# xen_teensy_motherboard_12cv_mki.net
KiCad netlist of a schematic drawn in EAGLE
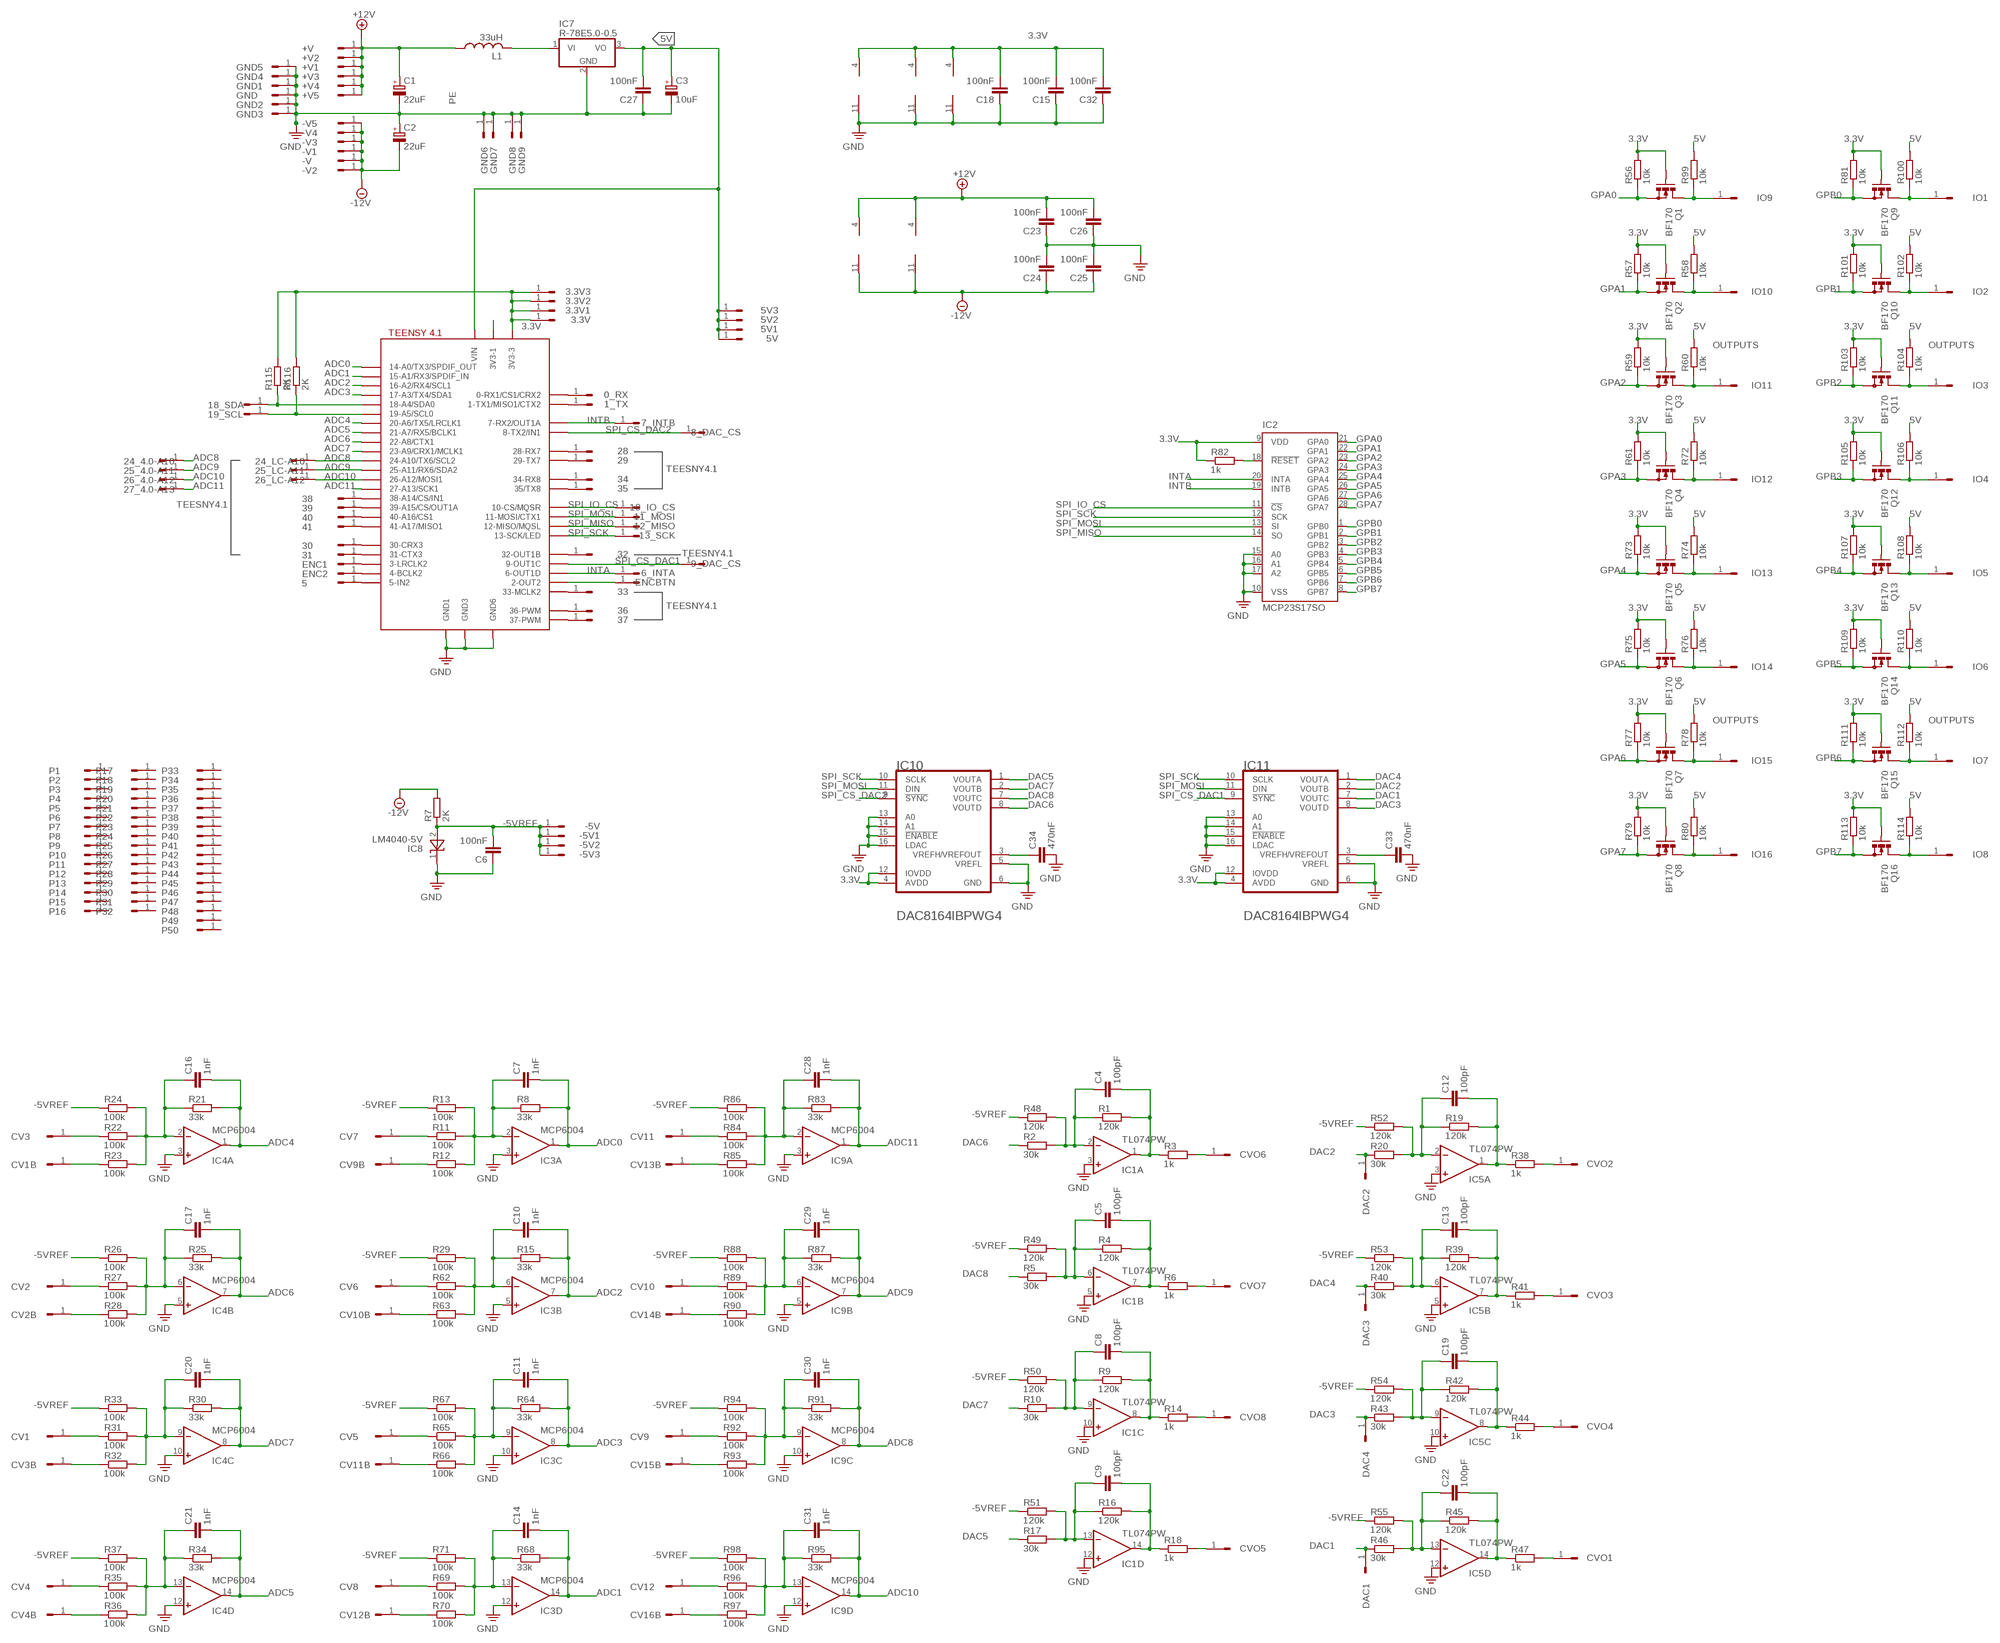
[diagram p0: schematic, sheet 1]

(export (version "E")
  (design (tool "Eeschema 10.0.6"))
  (components
    (comp (ref "+V")
      (value "HEADER/MALE/01")
      (footprint "eagle-import:HEADER_MALE_01")
      (fields (field (name "SPICEPREFIX") "X"))
      (libsource (lib "eagle-import") (part "HEADER/MALE/01"))
    )
    (comp (ref "+V1")
      (value "HEADER/MALE/01")
      (footprint "eagle-import:HEADER_MALE_01")
      (fields (field (name "SPICEPREFIX") "X"))
      (libsource (lib "eagle-import") (part "HEADER/MALE/01"))
    )
    (comp (ref "+V2")
      (value "HEADER/MALE/01")
      (footprint "eagle-import:HEADER_MALE_01")
      (fields (field (name "SPICEPREFIX") "X"))
      (libsource (lib "eagle-import") (part "HEADER/MALE/01"))
    )
    (comp (ref "+V3")
      (value "HEADER/MALE/01")
      (footprint "eagle-import:HEADER_MALE_01")
      (fields (field (name "SPICEPREFIX") "X"))
      (libsource (lib "eagle-import") (part "HEADER/MALE/01"))
    )
    (comp (ref "+V4")
      (value "HEADER/MALE/01")
      (footprint "eagle-import:HEADER_MALE_01")
      (fields (field (name "SPICEPREFIX") "X"))
      (libsource (lib "eagle-import") (part "HEADER/MALE/01"))
    )
    (comp (ref "+V5")
      (value "HEADER/MALE/01")
      (footprint "eagle-import:HEADER_MALE_01")
      (fields (field (name "SPICEPREFIX") "X"))
      (libsource (lib "eagle-import") (part "HEADER/MALE/01"))
    )
    (comp (ref "-5V")
      (value "HEADER/MALE/01")
      (footprint "eagle-import:HEADER_MALE_01")
      (fields (field (name "SPICEPREFIX") "X"))
      (libsource (lib "eagle-import") (part "HEADER/MALE/01"))
    )
    (comp (ref "-5V1")
      (value "HEADER/MALE/01")
      (footprint "eagle-import:HEADER_MALE_01")
      (fields (field (name "SPICEPREFIX") "X"))
      (libsource (lib "eagle-import") (part "HEADER/MALE/01"))
    )
    (comp (ref "-5V2")
      (value "HEADER/MALE/01")
      (footprint "eagle-import:HEADER_MALE_01")
      (fields (field (name "SPICEPREFIX") "X"))
      (libsource (lib "eagle-import") (part "HEADER/MALE/01"))
    )
    (comp (ref "-5V3")
      (value "HEADER/MALE/01")
      (footprint "eagle-import:HEADER_MALE_01")
      (fields (field (name "SPICEPREFIX") "X"))
      (libsource (lib "eagle-import") (part "HEADER/MALE/01"))
    )
    (comp (ref "-V")
      (value "HEADER/MALE/01")
      (footprint "eagle-import:HEADER_MALE_01")
      (fields (field (name "SPICEPREFIX") "X"))
      (libsource (lib "eagle-import") (part "HEADER/MALE/01"))
    )
    (comp (ref "-V1")
      (value "HEADER/MALE/01")
      (footprint "eagle-import:HEADER_MALE_01")
      (fields (field (name "SPICEPREFIX") "X"))
      (libsource (lib "eagle-import") (part "HEADER/MALE/01"))
    )
    (comp (ref "-V2")
      (value "HEADER/MALE/01")
      (footprint "eagle-import:HEADER_MALE_01")
      (fields (field (name "SPICEPREFIX") "X"))
      (libsource (lib "eagle-import") (part "HEADER/MALE/01"))
    )
    (comp (ref "-V3")
      (value "HEADER/MALE/01")
      (footprint "eagle-import:HEADER_MALE_01")
      (fields (field (name "SPICEPREFIX") "X"))
      (libsource (lib "eagle-import") (part "HEADER/MALE/01"))
    )
    (comp (ref "-V4")
      (value "HEADER/MALE/01")
      (footprint "eagle-import:HEADER_MALE_01")
      (fields (field (name "SPICEPREFIX") "X"))
      (libsource (lib "eagle-import") (part "HEADER/MALE/01"))
    )
    (comp (ref "-V5")
      (value "HEADER/MALE/01")
      (footprint "eagle-import:HEADER_MALE_01")
      (fields (field (name "SPICEPREFIX") "X"))
      (libsource (lib "eagle-import") (part "HEADER/MALE/01"))
    )
    (comp (ref "0_RX")
      (value "HEADER/MALE/01")
      (footprint "eagle-import:HEADER_MALE_01")
      (fields (field (name "SPICEPREFIX") "X"))
      (libsource (lib "eagle-import") (part "HEADER/MALE/01"))
    )
    (comp (ref "1_TX")
      (value "HEADER/MALE/01")
      (footprint "eagle-import:HEADER_MALE_01")
      (fields (field (name "SPICEPREFIX") "X"))
      (libsource (lib "eagle-import") (part "HEADER/MALE/01"))
    )
    (comp (ref "3.3V")
      (value "HEADER/MALE/01")
      (footprint "eagle-import:HEADER_MALE_01")
      (fields (field (name "SPICEPREFIX") "X"))
      (libsource (lib "eagle-import") (part "HEADER/MALE/01"))
    )
    (comp (ref "3.3V1")
      (value "HEADER/MALE/01")
      (footprint "eagle-import:HEADER_MALE_01")
      (fields (field (name "SPICEPREFIX") "X"))
      (libsource (lib "eagle-import") (part "HEADER/MALE/01"))
    )
    (comp (ref "3.3V2")
      (value "HEADER/MALE/01")
      (footprint "eagle-import:HEADER_MALE_01")
      (fields (field (name "SPICEPREFIX") "X"))
      (libsource (lib "eagle-import") (part "HEADER/MALE/01"))
    )
    (comp (ref "3.3V3")
      (value "HEADER/MALE/01")
      (footprint "eagle-import:HEADER_MALE_01")
      (fields (field (name "SPICEPREFIX") "X"))
      (libsource (lib "eagle-import") (part "HEADER/MALE/01"))
    )
    (comp (ref "5")
      (value "HEADER/MALE/01")
      (footprint "eagle-import:HEADER_MALE_01")
      (fields (field (name "SPICEPREFIX") "X"))
      (libsource (lib "eagle-import") (part "HEADER/MALE/01"))
    )
    (comp (ref "5V")
      (value "HEADER/MALE/01")
      (footprint "eagle-import:HEADER_MALE_01")
      (fields (field (name "SPICEPREFIX") "X"))
      (libsource (lib "eagle-import") (part "HEADER/MALE/01"))
    )
    (comp (ref "5V1")
      (value "HEADER/MALE/01")
      (footprint "eagle-import:HEADER_MALE_01")
      (fields (field (name "SPICEPREFIX") "X"))
      (libsource (lib "eagle-import") (part "HEADER/MALE/01"))
    )
    (comp (ref "5V2")
      (value "HEADER/MALE/01")
      (footprint "eagle-import:HEADER_MALE_01")
      (fields (field (name "SPICEPREFIX") "X"))
      (libsource (lib "eagle-import") (part "HEADER/MALE/01"))
    )
    (comp (ref "5V3")
      (value "HEADER/MALE/01")
      (footprint "eagle-import:HEADER_MALE_01")
      (fields (field (name "SPICEPREFIX") "X"))
      (libsource (lib "eagle-import") (part "HEADER/MALE/01"))
    )
    (comp (ref "6_INTA")
      (value "HEADER/MALE/01")
      (footprint "eagle-import:HEADER_MALE_01")
      (fields (field (name "SPICEPREFIX") "X"))
      (libsource (lib "eagle-import") (part "HEADER/MALE/01"))
    )
    (comp (ref "7_INTB")
      (value "HEADER/MALE/01")
      (footprint "eagle-import:HEADER_MALE_01")
      (fields (field (name "SPICEPREFIX") "X"))
      (libsource (lib "eagle-import") (part "HEADER/MALE/01"))
    )
    (comp (ref "8_DAC_CS")
      (value "HEADER/MALE/01")
      (footprint "eagle-import:HEADER_MALE_01")
      (fields (field (name "SPICEPREFIX") "X"))
      (libsource (lib "eagle-import") (part "HEADER/MALE/01"))
    )
    (comp (ref "9_DAC_CS")
      (value "HEADER/MALE/01")
      (footprint "eagle-import:HEADER_MALE_01")
      (fields (field (name "SPICEPREFIX") "X"))
      (libsource (lib "eagle-import") (part "HEADER/MALE/01"))
    )
    (comp (ref "10_IO_CS")
      (value "HEADER/MALE/01")
      (footprint "eagle-import:HEADER_MALE_01")
      (fields (field (name "SPICEPREFIX") "X"))
      (libsource (lib "eagle-import") (part "HEADER/MALE/01"))
    )
    (comp (ref "11_MOSI")
      (value "HEADER/MALE/01")
      (footprint "eagle-import:HEADER_MALE_01")
      (fields (field (name "SPICEPREFIX") "X"))
      (libsource (lib "eagle-import") (part "HEADER/MALE/01"))
    )
    (comp (ref "12_MISO")
      (value "HEADER/MALE/01")
      (footprint "eagle-import:HEADER_MALE_01")
      (fields (field (name "SPICEPREFIX") "X"))
      (libsource (lib "eagle-import") (part "HEADER/MALE/01"))
    )
    (comp (ref "13_SCK")
      (value "HEADER/MALE/01")
      (footprint "eagle-import:HEADER_MALE_01")
      (fields (field (name "SPICEPREFIX") "X"))
      (libsource (lib "eagle-import") (part "HEADER/MALE/01"))
    )
    (comp (ref "18_SDA")
      (value "HEADER/MALE/01")
      (footprint "eagle-import:HEADER_MALE_01")
      (fields (field (name "SPICEPREFIX") "X"))
      (libsource (lib "eagle-import") (part "HEADER/MALE/01"))
    )
    (comp (ref "19_SCL")
      (value "HEADER/MALE/01")
      (footprint "eagle-import:HEADER_MALE_01")
      (fields (field (name "SPICEPREFIX") "X"))
      (libsource (lib "eagle-import") (part "HEADER/MALE/01"))
    )
    (comp (ref "24_4.0-A10")
      (value "HEADER/MALE/01")
      (footprint "eagle-import:HEADER_MALE_01")
      (fields (field (name "SPICEPREFIX") "X"))
      (libsource (lib "eagle-import") (part "HEADER/MALE/01"))
    )
    (comp (ref "24_LC-A10")
      (value "HEADER/MALE/01")
      (footprint "eagle-import:HEADER_MALE_01")
      (fields (field (name "SPICEPREFIX") "X"))
      (libsource (lib "eagle-import") (part "HEADER/MALE/01"))
    )
    (comp (ref "25_4.0-A11")
      (value "HEADER/MALE/01")
      (footprint "eagle-import:HEADER_MALE_01")
      (fields (field (name "SPICEPREFIX") "X"))
      (libsource (lib "eagle-import") (part "HEADER/MALE/01"))
    )
    (comp (ref "25_LC-A11")
      (value "HEADER/MALE/01")
      (footprint "eagle-import:HEADER_MALE_01")
      (fields (field (name "SPICEPREFIX") "X"))
      (libsource (lib "eagle-import") (part "HEADER/MALE/01"))
    )
    (comp (ref "26_4.0-A12")
      (value "HEADER/MALE/01")
      (footprint "eagle-import:HEADER_MALE_01")
      (fields (field (name "SPICEPREFIX") "X"))
      (libsource (lib "eagle-import") (part "HEADER/MALE/01"))
    )
    (comp (ref "26_LC-A12")
      (value "HEADER/MALE/01")
      (footprint "eagle-import:HEADER_MALE_01")
      (fields (field (name "SPICEPREFIX") "X"))
      (libsource (lib "eagle-import") (part "HEADER/MALE/01"))
    )
    (comp (ref "27_4.0-A13")
      (value "HEADER/MALE/01")
      (footprint "eagle-import:HEADER_MALE_01")
      (fields (field (name "SPICEPREFIX") "X"))
      (libsource (lib "eagle-import") (part "HEADER/MALE/01"))
    )
    (comp (ref "28")
      (value "HEADER/MALE/01")
      (footprint "eagle-import:HEADER_MALE_01")
      (fields (field (name "SPICEPREFIX") "X"))
      (libsource (lib "eagle-import") (part "HEADER/MALE/01"))
    )
    (comp (ref "29")
      (value "HEADER/MALE/01")
      (footprint "eagle-import:HEADER_MALE_01")
      (fields (field (name "SPICEPREFIX") "X"))
      (libsource (lib "eagle-import") (part "HEADER/MALE/01"))
    )
    (comp (ref "30")
      (value "HEADER/MALE/01")
      (footprint "eagle-import:HEADER_MALE_01")
      (fields (field (name "SPICEPREFIX") "X"))
      (libsource (lib "eagle-import") (part "HEADER/MALE/01"))
    )
    (comp (ref "31")
      (value "HEADER/MALE/01")
      (footprint "eagle-import:HEADER_MALE_01")
      (fields (field (name "SPICEPREFIX") "X"))
      (libsource (lib "eagle-import") (part "HEADER/MALE/01"))
    )
    (comp (ref "32")
      (value "HEADER/MALE/01")
      (footprint "eagle-import:HEADER_MALE_01")
      (fields (field (name "SPICEPREFIX") "X"))
      (libsource (lib "eagle-import") (part "HEADER/MALE/01"))
    )
    (comp (ref "33")
      (value "HEADER/MALE/01")
      (footprint "eagle-import:HEADER_MALE_01")
      (fields (field (name "SPICEPREFIX") "X"))
      (libsource (lib "eagle-import") (part "HEADER/MALE/01"))
    )
    (comp (ref "34")
      (value "HEADER/MALE/01")
      (footprint "eagle-import:HEADER_MALE_01")
      (fields (field (name "SPICEPREFIX") "X"))
      (libsource (lib "eagle-import") (part "HEADER/MALE/01"))
    )
    (comp (ref "35")
      (value "HEADER/MALE/01")
      (footprint "eagle-import:HEADER_MALE_01")
      (fields (field (name "SPICEPREFIX") "X"))
      (libsource (lib "eagle-import") (part "HEADER/MALE/01"))
    )
    (comp (ref "36")
      (value "HEADER/MALE/01")
      (footprint "eagle-import:HEADER_MALE_01")
      (fields (field (name "SPICEPREFIX") "X"))
      (libsource (lib "eagle-import") (part "HEADER/MALE/01"))
    )
    (comp (ref "37")
      (value "HEADER/MALE/01")
      (footprint "eagle-import:HEADER_MALE_01")
      (fields (field (name "SPICEPREFIX") "X"))
      (libsource (lib "eagle-import") (part "HEADER/MALE/01"))
    )
    (comp (ref "38")
      (value "HEADER/MALE/01")
      (footprint "eagle-import:HEADER_MALE_01")
      (fields (field (name "SPICEPREFIX") "X"))
      (libsource (lib "eagle-import") (part "HEADER/MALE/01"))
    )
    (comp (ref "39")
      (value "HEADER/MALE/01")
      (footprint "eagle-import:HEADER_MALE_01")
      (fields (field (name "SPICEPREFIX") "X"))
      (libsource (lib "eagle-import") (part "HEADER/MALE/01"))
    )
    (comp (ref "40")
      (value "HEADER/MALE/01")
      (footprint "eagle-import:HEADER_MALE_01")
      (fields (field (name "SPICEPREFIX") "X"))
      (libsource (lib "eagle-import") (part "HEADER/MALE/01"))
    )
    (comp (ref "41")
      (value "HEADER/MALE/01")
      (footprint "eagle-import:HEADER_MALE_01")
      (fields (field (name "SPICEPREFIX") "X"))
      (libsource (lib "eagle-import") (part "HEADER/MALE/01"))
    )
    (comp (ref "C1")
      (value "22uF")
      (footprint "eagle-import:SV-C")
      (fields (field (name "SPICEPREFIX") "C"))
      (libsource (lib "eagle-import") (part "CAPACITOR/POLARIZEDSMDC"))
    )
    (comp (ref "C2")
      (value "22uF")
      (footprint "eagle-import:SV-C")
      (fields (field (name "SPICEPREFIX") "C"))
      (libsource (lib "eagle-import") (part "CAPACITOR/POLARIZEDSMDC"))
    )
    (comp (ref "C3")
      (value "10uF")
      (footprint "eagle-import:SV-B")
      (fields (field (name "SPICEPREFIX") "C"))
      (libsource (lib "eagle-import") (part "CAPACITOR/POLARIZEDSMDB"))
    )
    (comp (ref "C4")
      (value "100pF")
      (footprint "eagle-import:C0603")
      (libsource (lib "eagle-import") (part "CAPACITORC0603"))
    )
    (comp (ref "C5")
      (value "100pF")
      (footprint "eagle-import:C0603")
      (libsource (lib "eagle-import") (part "CAPACITORC0603"))
    )
    (comp (ref "C6")
      (value "100nF")
      (footprint "eagle-import:C0603")
      (libsource (lib "eagle-import") (part "CAPACITORC0603"))
    )
    (comp (ref "C7")
      (value "1nF")
      (footprint "eagle-import:C0603")
      (libsource (lib "eagle-import") (part "CAPACITORC0603"))
    )
    (comp (ref "C8")
      (value "100pF")
      (footprint "eagle-import:C0603")
      (libsource (lib "eagle-import") (part "CAPACITORC0603"))
    )
    (comp (ref "C9")
      (value "100pF")
      (footprint "eagle-import:C0603")
      (libsource (lib "eagle-import") (part "CAPACITORC0603"))
    )
    (comp (ref "C10")
      (value "1nF")
      (footprint "eagle-import:C0603")
      (libsource (lib "eagle-import") (part "CAPACITORC0603"))
    )
    (comp (ref "C11")
      (value "1nF")
      (footprint "eagle-import:C0603")
      (libsource (lib "eagle-import") (part "CAPACITORC0603"))
    )
    (comp (ref "C12")
      (value "100pF")
      (footprint "eagle-import:C0603")
      (libsource (lib "eagle-import") (part "CAPACITORC0603"))
    )
    (comp (ref "C13")
      (value "100pF")
      (footprint "eagle-import:C0603")
      (libsource (lib "eagle-import") (part "CAPACITORC0603"))
    )
    (comp (ref "C14")
      (value "1nF")
      (footprint "eagle-import:C0603")
      (libsource (lib "eagle-import") (part "CAPACITORC0603"))
    )
    (comp (ref "C15")
      (value "100nF")
      (footprint "eagle-import:C0603")
      (libsource (lib "eagle-import") (part "CAPACITORC0603"))
    )
    (comp (ref "C16")
      (value "1nF")
      (footprint "eagle-import:C0603")
      (libsource (lib "eagle-import") (part "CAPACITORC0603"))
    )
    (comp (ref "C17")
      (value "1nF")
      (footprint "eagle-import:C0603")
      (libsource (lib "eagle-import") (part "CAPACITORC0603"))
    )
    (comp (ref "C18")
      (value "100nF")
      (footprint "eagle-import:C0603")
      (libsource (lib "eagle-import") (part "CAPACITORC0603"))
    )
    (comp (ref "C19")
      (value "100pF")
      (footprint "eagle-import:C0603")
      (libsource (lib "eagle-import") (part "CAPACITORC0603"))
    )
    (comp (ref "C20")
      (value "1nF")
      (footprint "eagle-import:C0603")
      (libsource (lib "eagle-import") (part "CAPACITORC0603"))
    )
    (comp (ref "C21")
      (value "1nF")
      (footprint "eagle-import:C0603")
      (libsource (lib "eagle-import") (part "CAPACITORC0603"))
    )
    (comp (ref "C22")
      (value "100pF")
      (footprint "eagle-import:C0603")
      (libsource (lib "eagle-import") (part "CAPACITORC0603"))
    )
    (comp (ref "C23")
      (value "100nF")
      (footprint "eagle-import:C0603")
      (libsource (lib "eagle-import") (part "CAPACITORC0603"))
    )
    (comp (ref "C24")
      (value "100nF")
      (footprint "eagle-import:C0603")
      (libsource (lib "eagle-import") (part "CAPACITORC0603"))
    )
    (comp (ref "C25")
      (value "100nF")
      (footprint "eagle-import:C0603")
      (libsource (lib "eagle-import") (part "CAPACITORC0603"))
    )
    (comp (ref "C26")
      (value "100nF")
      (footprint "eagle-import:C0603")
      (libsource (lib "eagle-import") (part "CAPACITORC0603"))
    )
    (comp (ref "C27")
      (value "100nF")
      (footprint "eagle-import:C0603")
      (libsource (lib "eagle-import") (part "CAPACITORC0603"))
    )
    (comp (ref "C28")
      (value "1nF")
      (footprint "eagle-import:C0603")
      (libsource (lib "eagle-import") (part "CAPACITORC0603"))
    )
    (comp (ref "C29")
      (value "1nF")
      (footprint "eagle-import:C0603")
      (libsource (lib "eagle-import") (part "CAPACITORC0603"))
    )
    (comp (ref "C30")
      (value "1nF")
      (footprint "eagle-import:C0603")
      (libsource (lib "eagle-import") (part "CAPACITORC0603"))
    )
    (comp (ref "C31")
      (value "1nF")
      (footprint "eagle-import:C0603")
      (libsource (lib "eagle-import") (part "CAPACITORC0603"))
    )
    (comp (ref "C32")
      (value "100nF")
      (footprint "eagle-import:C0603")
      (libsource (lib "eagle-import") (part "CAPACITORC0603"))
    )
    (comp (ref "C33")
      (value "470nF")
      (footprint "eagle-import:C0603")
      (libsource (lib "eagle-import") (part "CAPACITORC0603"))
    )
    (comp (ref "C34")
      (value "470nF")
      (footprint "eagle-import:C0603")
      (libsource (lib "eagle-import") (part "CAPACITORC0603"))
    )
    (comp (ref "CV1")
      (value "HEADER/MALE/01")
      (footprint "eagle-import:HEADER_MALE_01")
      (fields (field (name "SPICEPREFIX") "X"))
      (libsource (lib "eagle-import") (part "HEADER/MALE/01"))
    )
    (comp (ref "CV1B")
      (value "HEADER/MALE/01")
      (footprint "eagle-import:HEADER_MALE_01")
      (fields (field (name "SPICEPREFIX") "X"))
      (libsource (lib "eagle-import") (part "HEADER/MALE/01"))
    )
    (comp (ref "CV2")
      (value "HEADER/MALE/01")
      (footprint "eagle-import:HEADER_MALE_01")
      (fields (field (name "SPICEPREFIX") "X"))
      (libsource (lib "eagle-import") (part "HEADER/MALE/01"))
    )
    (comp (ref "CV2B")
      (value "HEADER/MALE/01")
      (footprint "eagle-import:HEADER_MALE_01")
      (fields (field (name "SPICEPREFIX") "X"))
      (libsource (lib "eagle-import") (part "HEADER/MALE/01"))
    )
    (comp (ref "CV3")
      (value "HEADER/MALE/01")
      (footprint "eagle-import:HEADER_MALE_01")
      (fields (field (name "SPICEPREFIX") "X"))
      (libsource (lib "eagle-import") (part "HEADER/MALE/01"))
    )
    (comp (ref "CV3B")
      (value "HEADER/MALE/01")
      (footprint "eagle-import:HEADER_MALE_01")
      (fields (field (name "SPICEPREFIX") "X"))
      (libsource (lib "eagle-import") (part "HEADER/MALE/01"))
    )
    (comp (ref "CV4")
      (value "HEADER/MALE/01")
      (footprint "eagle-import:HEADER_MALE_01")
      (fields (field (name "SPICEPREFIX") "X"))
      (libsource (lib "eagle-import") (part "HEADER/MALE/01"))
    )
    (comp (ref "CV4B")
      (value "HEADER/MALE/01")
      (footprint "eagle-import:HEADER_MALE_01")
      (fields (field (name "SPICEPREFIX") "X"))
      (libsource (lib "eagle-import") (part "HEADER/MALE/01"))
    )
    (comp (ref "CV5")
      (value "HEADER/MALE/01")
      (footprint "eagle-import:HEADER_MALE_01")
      (fields (field (name "SPICEPREFIX") "X"))
      (libsource (lib "eagle-import") (part "HEADER/MALE/01"))
    )
    (comp (ref "CV6")
      (value "HEADER/MALE/01")
      (footprint "eagle-import:HEADER_MALE_01")
      (fields (field (name "SPICEPREFIX") "X"))
      (libsource (lib "eagle-import") (part "HEADER/MALE/01"))
    )
    (comp (ref "CV7")
      (value "HEADER/MALE/01")
      (footprint "eagle-import:HEADER_MALE_01")
      (fields (field (name "SPICEPREFIX") "X"))
      (libsource (lib "eagle-import") (part "HEADER/MALE/01"))
    )
    (comp (ref "CV8")
      (value "HEADER/MALE/01")
      (footprint "eagle-import:HEADER_MALE_01")
      (fields (field (name "SPICEPREFIX") "X"))
      (libsource (lib "eagle-import") (part "HEADER/MALE/01"))
    )
    (comp (ref "CV9")
      (value "HEADER/MALE/01")
      (footprint "eagle-import:HEADER_MALE_01")
      (fields (field (name "SPICEPREFIX") "X"))
      (libsource (lib "eagle-import") (part "HEADER/MALE/01"))
    )
    (comp (ref "CV9B")
      (value "HEADER/MALE/01")
      (footprint "eagle-import:HEADER_MALE_01")
      (fields (field (name "SPICEPREFIX") "X"))
      (libsource (lib "eagle-import") (part "HEADER/MALE/01"))
    )
    (comp (ref "CV10")
      (value "HEADER/MALE/01")
      (footprint "eagle-import:HEADER_MALE_01")
      (fields (field (name "SPICEPREFIX") "X"))
      (libsource (lib "eagle-import") (part "HEADER/MALE/01"))
    )
    (comp (ref "CV10B")
      (value "HEADER/MALE/01")
      (footprint "eagle-import:HEADER_MALE_01")
      (fields (field (name "SPICEPREFIX") "X"))
      (libsource (lib "eagle-import") (part "HEADER/MALE/01"))
    )
    (comp (ref "CV11")
      (value "HEADER/MALE/01")
      (footprint "eagle-import:HEADER_MALE_01")
      (fields (field (name "SPICEPREFIX") "X"))
      (libsource (lib "eagle-import") (part "HEADER/MALE/01"))
    )
    (comp (ref "CV11B")
      (value "HEADER/MALE/01")
      (footprint "eagle-import:HEADER_MALE_01")
      (fields (field (name "SPICEPREFIX") "X"))
      (libsource (lib "eagle-import") (part "HEADER/MALE/01"))
    )
    (comp (ref "CV12")
      (value "HEADER/MALE/01")
      (footprint "eagle-import:HEADER_MALE_01")
      (fields (field (name "SPICEPREFIX") "X"))
      (libsource (lib "eagle-import") (part "HEADER/MALE/01"))
    )
    (comp (ref "CV12B")
      (value "HEADER/MALE/01")
      (footprint "eagle-import:HEADER_MALE_01")
      (fields (field (name "SPICEPREFIX") "X"))
      (libsource (lib "eagle-import") (part "HEADER/MALE/01"))
    )
    (comp (ref "CV13B")
      (value "HEADER/MALE/01")
      (footprint "eagle-import:HEADER_MALE_01")
      (fields (field (name "SPICEPREFIX") "X"))
      (libsource (lib "eagle-import") (part "HEADER/MALE/01"))
    )
    (comp (ref "CV14B")
      (value "HEADER/MALE/01")
      (footprint "eagle-import:HEADER_MALE_01")
      (fields (field (name "SPICEPREFIX") "X"))
      (libsource (lib "eagle-import") (part "HEADER/MALE/01"))
    )
    (comp (ref "CV15B")
      (value "HEADER/MALE/01")
      (footprint "eagle-import:HEADER_MALE_01")
      (fields (field (name "SPICEPREFIX") "X"))
      (libsource (lib "eagle-import") (part "HEADER/MALE/01"))
    )
    (comp (ref "CV16B")
      (value "HEADER/MALE/01")
      (footprint "eagle-import:HEADER_MALE_01")
      (fields (field (name "SPICEPREFIX") "X"))
      (libsource (lib "eagle-import") (part "HEADER/MALE/01"))
    )
    (comp (ref "CVO1")
      (value "HEADER/MALE/01")
      (footprint "eagle-import:HEADER_MALE_01")
      (fields (field (name "SPICEPREFIX") "X"))
      (libsource (lib "eagle-import") (part "HEADER/MALE/01"))
    )
    (comp (ref "CVO2")
      (value "HEADER/MALE/01")
      (footprint "eagle-import:HEADER_MALE_01")
      (fields (field (name "SPICEPREFIX") "X"))
      (libsource (lib "eagle-import") (part "HEADER/MALE/01"))
    )
    (comp (ref "CVO3")
      (value "HEADER/MALE/01")
      (footprint "eagle-import:HEADER_MALE_01")
      (fields (field (name "SPICEPREFIX") "X"))
      (libsource (lib "eagle-import") (part "HEADER/MALE/01"))
    )
    (comp (ref "CVO4")
      (value "HEADER/MALE/01")
      (footprint "eagle-import:HEADER_MALE_01")
      (fields (field (name "SPICEPREFIX") "X"))
      (libsource (lib "eagle-import") (part "HEADER/MALE/01"))
    )
    (comp (ref "CVO5")
      (value "HEADER/MALE/01")
      (footprint "eagle-import:HEADER_MALE_01")
      (fields (field (name "SPICEPREFIX") "X"))
      (libsource (lib "eagle-import") (part "HEADER/MALE/01"))
    )
    (comp (ref "CVO6")
      (value "HEADER/MALE/01")
      (footprint "eagle-import:HEADER_MALE_01")
      (fields (field (name "SPICEPREFIX") "X"))
      (libsource (lib "eagle-import") (part "HEADER/MALE/01"))
    )
    (comp (ref "CVO7")
      (value "HEADER/MALE/01")
      (footprint "eagle-import:HEADER_MALE_01")
      (fields (field (name "SPICEPREFIX") "X"))
      (libsource (lib "eagle-import") (part "HEADER/MALE/01"))
    )
    (comp (ref "CVO8")
      (value "HEADER/MALE/01")
      (footprint "eagle-import:HEADER_MALE_01")
      (fields (field (name "SPICEPREFIX") "X"))
      (libsource (lib "eagle-import") (part "HEADER/MALE/01"))
    )
    (comp (ref "DAC1")
      (value "HEADER/MALE/01")
      (footprint "eagle-import:HEADER_MALE_01")
      (fields (field (name "SPICEPREFIX") "X"))
      (libsource (lib "eagle-import") (part "HEADER/MALE/01"))
    )
    (comp (ref "DAC2")
      (value "HEADER/MALE/01")
      (footprint "eagle-import:HEADER_MALE_01")
      (fields (field (name "SPICEPREFIX") "X"))
      (libsource (lib "eagle-import") (part "HEADER/MALE/01"))
    )
    (comp (ref "DAC3")
      (value "HEADER/MALE/01")
      (footprint "eagle-import:HEADER_MALE_01")
      (fields (field (name "SPICEPREFIX") "X"))
      (libsource (lib "eagle-import") (part "HEADER/MALE/01"))
    )
    (comp (ref "DAC4")
      (value "HEADER/MALE/01")
      (footprint "eagle-import:HEADER_MALE_01")
      (fields (field (name "SPICEPREFIX") "X"))
      (libsource (lib "eagle-import") (part "HEADER/MALE/01"))
    )
    (comp (ref "ENC1")
      (value "HEADER/MALE/01")
      (footprint "eagle-import:HEADER_MALE_01")
      (fields (field (name "SPICEPREFIX") "X"))
      (libsource (lib "eagle-import") (part "HEADER/MALE/01"))
    )
    (comp (ref "ENC2")
      (value "HEADER/MALE/01")
      (footprint "eagle-import:HEADER_MALE_01")
      (fields (field (name "SPICEPREFIX") "X"))
      (libsource (lib "eagle-import") (part "HEADER/MALE/01"))
    )
    (comp (ref "ENCBTN")
      (value "HEADER/MALE/01")
      (footprint "eagle-import:HEADER_MALE_01")
      (fields (field (name "SPICEPREFIX") "X"))
      (libsource (lib "eagle-import") (part "HEADER/MALE/01"))
    )
    (comp (ref "GND")
      (value "HEADER/MALE/01")
      (footprint "eagle-import:HEADER_MALE_01")
      (fields (field (name "SPICEPREFIX") "X"))
      (libsource (lib "eagle-import") (part "HEADER/MALE/01"))
    )
    (comp (ref "GND1")
      (value "HEADER/MALE/01")
      (footprint "eagle-import:HEADER_MALE_01")
      (fields (field (name "SPICEPREFIX") "X"))
      (libsource (lib "eagle-import") (part "HEADER/MALE/01"))
    )
    (comp (ref "GND2")
      (value "HEADER/MALE/01")
      (footprint "eagle-import:HEADER_MALE_01")
      (fields (field (name "SPICEPREFIX") "X"))
      (libsource (lib "eagle-import") (part "HEADER/MALE/01"))
    )
    (comp (ref "GND3")
      (value "HEADER/MALE/01")
      (footprint "eagle-import:HEADER_MALE_01")
      (fields (field (name "SPICEPREFIX") "X"))
      (libsource (lib "eagle-import") (part "HEADER/MALE/01"))
    )
    (comp (ref "GND4")
      (value "HEADER/MALE/01")
      (footprint "eagle-import:HEADER_MALE_01")
      (fields (field (name "SPICEPREFIX") "X"))
      (libsource (lib "eagle-import") (part "HEADER/MALE/01"))
    )
    (comp (ref "GND5")
      (value "HEADER/MALE/01")
      (footprint "eagle-import:HEADER_MALE_01")
      (fields (field (name "SPICEPREFIX") "X"))
      (libsource (lib "eagle-import") (part "HEADER/MALE/01"))
    )
    (comp (ref "GND6")
      (value "HEADER/MALE/01")
      (footprint "eagle-import:HEADER_MALE_01")
      (fields (field (name "SPICEPREFIX") "X"))
      (libsource (lib "eagle-import") (part "HEADER/MALE/01"))
    )
    (comp (ref "GND7")
      (value "HEADER/MALE/01")
      (footprint "eagle-import:HEADER_MALE_01")
      (fields (field (name "SPICEPREFIX") "X"))
      (libsource (lib "eagle-import") (part "HEADER/MALE/01"))
    )
    (comp (ref "GND8")
      (value "HEADER/MALE/01")
      (footprint "eagle-import:HEADER_MALE_01")
      (fields (field (name "SPICEPREFIX") "X"))
      (libsource (lib "eagle-import") (part "HEADER/MALE/01"))
    )
    (comp (ref "GND9")
      (value "HEADER/MALE/01")
      (footprint "eagle-import:HEADER_MALE_01")
      (fields (field (name "SPICEPREFIX") "X"))
      (libsource (lib "eagle-import") (part "HEADER/MALE/01"))
    )
    (comp (ref "IC1")
      (value "TL074PW")
      (footprint "eagle-import:TSSOP14")
      (libsource (lib "eagle-import") (part "TL074PW"))
    )
    (comp (ref "IC2")
      (value "MCP23S17SO")
      (footprint "eagle-import:SO28W")
      (fields (field (name "MF") "MICROCHIP") (field (name "MPN") "MCP23S17-E/SO"))
      (libsource (lib "eagle-import") (part "MCP23S17SO"))
    )
    (comp (ref "IC3")
      (value "MCP6004")
      (footprint "eagle-import:TSSOP14")
      (libsource (lib "eagle-import") (part "TL074PW"))
    )
    (comp (ref "IC4")
      (value "MCP6004")
      (footprint "eagle-import:TSSOP14")
      (libsource (lib "eagle-import") (part "TL074PW"))
    )
    (comp (ref "IC5")
      (value "TL074PW")
      (footprint "eagle-import:TSSOP14")
      (libsource (lib "eagle-import") (part "TL074PW"))
    )
    (comp (ref "IC6")
      (value "TEENSY41-OUTER")
      (footprint "eagle-import:TENNSY41-OUTER")
      (libsource (lib "eagle-import") (part "TEENSY41-OUTER"))
    )
    (comp (ref "IC7")
      (value "R-78E5.0-0.5")
      (footprint "eagle-import:WE78")
      (libsource (lib "eagle-import") (part "WE173950378"))
    )
    (comp (ref "IC8")
      (value "LM4040-5V")
      (footprint "eagle-import:SOT-23")
      (libsource (lib "eagle-import") (part "LM4040CYM3-2.5"))
    )
    (comp (ref "IC9")
      (value "MCP6004")
      (footprint "eagle-import:TSSOP14")
      (libsource (lib "eagle-import") (part "TL074PW"))
    )
    (comp (ref "IC10")
      (value "TEXAS_INSTRUMENTS_DAC8164IBPWG4TEXAS_INSTRUMENTS_DAC8164IBPWG4_0_1")
      (footprint "eagle-import:TEXAS_INSTRUMENTS_DAC8164IBPWG4_1")
      (fields (field (name "MF") "Texas Instruments") (field (name "MPN") "DAC8164IBPWG4"))
      (libsource (lib "eagle-import") (part "TEXAS_INSTRUMENTS_DAC8164IBPWG4TEXAS_INSTRUMENTS_DAC8164IBPWG4_0_1"))
    )
    (comp (ref "IC11")
      (value "TEXAS_INSTRUMENTS_DAC8164IBPWG4TEXAS_INSTRUMENTS_DAC8164IBPWG4_0_1")
      (footprint "eagle-import:TEXAS_INSTRUMENTS_DAC8164IBPWG4_1")
      (fields (field (name "MF") "Texas Instruments") (field (name "MPN") "DAC8164IBPWG4"))
      (libsource (lib "eagle-import") (part "TEXAS_INSTRUMENTS_DAC8164IBPWG4TEXAS_INSTRUMENTS_DAC8164IBPWG4_0_1"))
    )
    (comp (ref "IO1")
      (value "HEADER/MALE/01")
      (footprint "eagle-import:HEADER_MALE_01")
      (fields (field (name "SPICEPREFIX") "X"))
      (libsource (lib "eagle-import") (part "HEADER/MALE/01"))
    )
    (comp (ref "IO2")
      (value "HEADER/MALE/01")
      (footprint "eagle-import:HEADER_MALE_01")
      (fields (field (name "SPICEPREFIX") "X"))
      (libsource (lib "eagle-import") (part "HEADER/MALE/01"))
    )
    (comp (ref "IO3")
      (value "HEADER/MALE/01")
      (footprint "eagle-import:HEADER_MALE_01")
      (fields (field (name "SPICEPREFIX") "X"))
      (libsource (lib "eagle-import") (part "HEADER/MALE/01"))
    )
    (comp (ref "IO4")
      (value "HEADER/MALE/01")
      (footprint "eagle-import:HEADER_MALE_01")
      (fields (field (name "SPICEPREFIX") "X"))
      (libsource (lib "eagle-import") (part "HEADER/MALE/01"))
    )
    (comp (ref "IO5")
      (value "HEADER/MALE/01")
      (footprint "eagle-import:HEADER_MALE_01")
      (fields (field (name "SPICEPREFIX") "X"))
      (libsource (lib "eagle-import") (part "HEADER/MALE/01"))
    )
    (comp (ref "IO6")
      (value "HEADER/MALE/01")
      (footprint "eagle-import:HEADER_MALE_01")
      (fields (field (name "SPICEPREFIX") "X"))
      (libsource (lib "eagle-import") (part "HEADER/MALE/01"))
    )
    (comp (ref "IO7")
      (value "HEADER/MALE/01")
      (footprint "eagle-import:HEADER_MALE_01")
      (fields (field (name "SPICEPREFIX") "X"))
      (libsource (lib "eagle-import") (part "HEADER/MALE/01"))
    )
    (comp (ref "IO8")
      (value "HEADER/MALE/01")
      (footprint "eagle-import:HEADER_MALE_01")
      (fields (field (name "SPICEPREFIX") "X"))
      (libsource (lib "eagle-import") (part "HEADER/MALE/01"))
    )
    (comp (ref "IO9")
      (value "HEADER/MALE/01")
      (footprint "eagle-import:HEADER_MALE_01")
      (fields (field (name "SPICEPREFIX") "X"))
      (libsource (lib "eagle-import") (part "HEADER/MALE/01"))
    )
    (comp (ref "IO10")
      (value "HEADER/MALE/01")
      (footprint "eagle-import:HEADER_MALE_01")
      (fields (field (name "SPICEPREFIX") "X"))
      (libsource (lib "eagle-import") (part "HEADER/MALE/01"))
    )
    (comp (ref "IO11")
      (value "HEADER/MALE/01")
      (footprint "eagle-import:HEADER_MALE_01")
      (fields (field (name "SPICEPREFIX") "X"))
      (libsource (lib "eagle-import") (part "HEADER/MALE/01"))
    )
    (comp (ref "IO12")
      (value "HEADER/MALE/01")
      (footprint "eagle-import:HEADER_MALE_01")
      (fields (field (name "SPICEPREFIX") "X"))
      (libsource (lib "eagle-import") (part "HEADER/MALE/01"))
    )
    (comp (ref "IO13")
      (value "HEADER/MALE/01")
      (footprint "eagle-import:HEADER_MALE_01")
      (fields (field (name "SPICEPREFIX") "X"))
      (libsource (lib "eagle-import") (part "HEADER/MALE/01"))
    )
    (comp (ref "IO14")
      (value "HEADER/MALE/01")
      (footprint "eagle-import:HEADER_MALE_01")
      (fields (field (name "SPICEPREFIX") "X"))
      (libsource (lib "eagle-import") (part "HEADER/MALE/01"))
    )
    (comp (ref "IO15")
      (value "HEADER/MALE/01")
      (footprint "eagle-import:HEADER_MALE_01")
      (fields (field (name "SPICEPREFIX") "X"))
      (libsource (lib "eagle-import") (part "HEADER/MALE/01"))
    )
    (comp (ref "IO16")
      (value "HEADER/MALE/01")
      (footprint "eagle-import:HEADER_MALE_01")
      (fields (field (name "SPICEPREFIX") "X"))
      (libsource (lib "eagle-import") (part "HEADER/MALE/01"))
    )
    (comp (ref "L1")
      (value "33uH")
      (footprint "eagle-import:L2012C")
      (libsource (lib "eagle-import") (part "INDUCTORL2012C"))
    )
    (comp (ref "P1")
      (value "HEADER/MALE/01NOBORDER")
      (footprint "eagle-import:HEADER_MALE_01_NOBORDER")
      (fields (field (name "SPICEPREFIX") "X"))
      (libsource (lib "eagle-import") (part "HEADER/MALE/01NOBORDER"))
    )
    (comp (ref "P2")
      (value "HEADER/MALE/01NOBORDER")
      (footprint "eagle-import:HEADER_MALE_01_NOBORDER")
      (fields (field (name "SPICEPREFIX") "X"))
      (libsource (lib "eagle-import") (part "HEADER/MALE/01NOBORDER"))
    )
    (comp (ref "P3")
      (value "HEADER/MALE/01NOBORDER")
      (footprint "eagle-import:HEADER_MALE_01_NOBORDER")
      (fields (field (name "SPICEPREFIX") "X"))
      (libsource (lib "eagle-import") (part "HEADER/MALE/01NOBORDER"))
    )
    (comp (ref "P4")
      (value "HEADER/MALE/01NOBORDER")
      (footprint "eagle-import:HEADER_MALE_01_NOBORDER")
      (fields (field (name "SPICEPREFIX") "X"))
      (libsource (lib "eagle-import") (part "HEADER/MALE/01NOBORDER"))
    )
    (comp (ref "P5")
      (value "HEADER/MALE/01NOBORDER")
      (footprint "eagle-import:HEADER_MALE_01_NOBORDER")
      (fields (field (name "SPICEPREFIX") "X"))
      (libsource (lib "eagle-import") (part "HEADER/MALE/01NOBORDER"))
    )
    (comp (ref "P6")
      (value "HEADER/MALE/01NOBORDER")
      (footprint "eagle-import:HEADER_MALE_01_NOBORDER")
      (fields (field (name "SPICEPREFIX") "X"))
      (libsource (lib "eagle-import") (part "HEADER/MALE/01NOBORDER"))
    )
    (comp (ref "P7")
      (value "HEADER/MALE/01NOBORDER")
      (footprint "eagle-import:HEADER_MALE_01_NOBORDER")
      (fields (field (name "SPICEPREFIX") "X"))
      (libsource (lib "eagle-import") (part "HEADER/MALE/01NOBORDER"))
    )
    (comp (ref "P8")
      (value "HEADER/MALE/01NOBORDER")
      (footprint "eagle-import:HEADER_MALE_01_NOBORDER")
      (fields (field (name "SPICEPREFIX") "X"))
      (libsource (lib "eagle-import") (part "HEADER/MALE/01NOBORDER"))
    )
    (comp (ref "P9")
      (value "HEADER/MALE/01NOBORDER")
      (footprint "eagle-import:HEADER_MALE_01_NOBORDER")
      (fields (field (name "SPICEPREFIX") "X"))
      (libsource (lib "eagle-import") (part "HEADER/MALE/01NOBORDER"))
    )
    (comp (ref "P10")
      (value "HEADER/MALE/01NOBORDER")
      (footprint "eagle-import:HEADER_MALE_01_NOBORDER")
      (fields (field (name "SPICEPREFIX") "X"))
      (libsource (lib "eagle-import") (part "HEADER/MALE/01NOBORDER"))
    )
    (comp (ref "P11")
      (value "HEADER/MALE/01NOBORDER")
      (footprint "eagle-import:HEADER_MALE_01_NOBORDER")
      (fields (field (name "SPICEPREFIX") "X"))
      (libsource (lib "eagle-import") (part "HEADER/MALE/01NOBORDER"))
    )
    (comp (ref "P12")
      (value "HEADER/MALE/01NOBORDER")
      (footprint "eagle-import:HEADER_MALE_01_NOBORDER")
      (fields (field (name "SPICEPREFIX") "X"))
      (libsource (lib "eagle-import") (part "HEADER/MALE/01NOBORDER"))
    )
    (comp (ref "P13")
      (value "HEADER/MALE/01NOBORDER")
      (footprint "eagle-import:HEADER_MALE_01_NOBORDER")
      (fields (field (name "SPICEPREFIX") "X"))
      (libsource (lib "eagle-import") (part "HEADER/MALE/01NOBORDER"))
    )
    (comp (ref "P14")
      (value "HEADER/MALE/01NOBORDER")
      (footprint "eagle-import:HEADER_MALE_01_NOBORDER")
      (fields (field (name "SPICEPREFIX") "X"))
      (libsource (lib "eagle-import") (part "HEADER/MALE/01NOBORDER"))
    )
    (comp (ref "P15")
      (value "HEADER/MALE/01NOBORDER")
      (footprint "eagle-import:HEADER_MALE_01_NOBORDER")
      (fields (field (name "SPICEPREFIX") "X"))
      (libsource (lib "eagle-import") (part "HEADER/MALE/01NOBORDER"))
    )
    (comp (ref "P16")
      (value "HEADER/MALE/01NOBORDER")
      (footprint "eagle-import:HEADER_MALE_01_NOBORDER")
      (fields (field (name "SPICEPREFIX") "X"))
      (libsource (lib "eagle-import") (part "HEADER/MALE/01NOBORDER"))
    )
    (comp (ref "P17")
      (value "HEADER/MALE/01NOBORDER")
      (footprint "eagle-import:HEADER_MALE_01_NOBORDER")
      (fields (field (name "SPICEPREFIX") "X"))
      (libsource (lib "eagle-import") (part "HEADER/MALE/01NOBORDER"))
    )
    (comp (ref "P18")
      (value "HEADER/MALE/01NOBORDER")
      (footprint "eagle-import:HEADER_MALE_01_NOBORDER")
      (fields (field (name "SPICEPREFIX") "X"))
      (libsource (lib "eagle-import") (part "HEADER/MALE/01NOBORDER"))
    )
    (comp (ref "P19")
      (value "HEADER/MALE/01NOBORDER")
      (footprint "eagle-import:HEADER_MALE_01_NOBORDER")
      (fields (field (name "SPICEPREFIX") "X"))
      (libsource (lib "eagle-import") (part "HEADER/MALE/01NOBORDER"))
    )
    (comp (ref "P20")
      (value "HEADER/MALE/01NOBORDER")
      (footprint "eagle-import:HEADER_MALE_01_NOBORDER")
      (fields (field (name "SPICEPREFIX") "X"))
      (libsource (lib "eagle-import") (part "HEADER/MALE/01NOBORDER"))
    )
    (comp (ref "P21")
      (value "HEADER/MALE/01NOBORDER")
      (footprint "eagle-import:HEADER_MALE_01_NOBORDER")
      (fields (field (name "SPICEPREFIX") "X"))
      (libsource (lib "eagle-import") (part "HEADER/MALE/01NOBORDER"))
    )
    (comp (ref "P22")
      (value "HEADER/MALE/01NOBORDER")
      (footprint "eagle-import:HEADER_MALE_01_NOBORDER")
      (fields (field (name "SPICEPREFIX") "X"))
      (libsource (lib "eagle-import") (part "HEADER/MALE/01NOBORDER"))
    )
    (comp (ref "P23")
      (value "HEADER/MALE/01NOBORDER")
      (footprint "eagle-import:HEADER_MALE_01_NOBORDER")
      (fields (field (name "SPICEPREFIX") "X"))
      (libsource (lib "eagle-import") (part "HEADER/MALE/01NOBORDER"))
    )
    (comp (ref "P24")
      (value "HEADER/MALE/01NOBORDER")
      (footprint "eagle-import:HEADER_MALE_01_NOBORDER")
      (fields (field (name "SPICEPREFIX") "X"))
      (libsource (lib "eagle-import") (part "HEADER/MALE/01NOBORDER"))
    )
    (comp (ref "P25")
      (value "HEADER/MALE/01NOBORDER")
      (footprint "eagle-import:HEADER_MALE_01_NOBORDER")
      (fields (field (name "SPICEPREFIX") "X"))
      (libsource (lib "eagle-import") (part "HEADER/MALE/01NOBORDER"))
    )
    (comp (ref "P26")
      (value "HEADER/MALE/01NOBORDER")
      (footprint "eagle-import:HEADER_MALE_01_NOBORDER")
      (fields (field (name "SPICEPREFIX") "X"))
      (libsource (lib "eagle-import") (part "HEADER/MALE/01NOBORDER"))
    )
    (comp (ref "P27")
      (value "HEADER/MALE/01NOBORDER")
      (footprint "eagle-import:HEADER_MALE_01_NOBORDER")
      (fields (field (name "SPICEPREFIX") "X"))
      (libsource (lib "eagle-import") (part "HEADER/MALE/01NOBORDER"))
    )
    (comp (ref "P28")
      (value "HEADER/MALE/01NOBORDER")
      (footprint "eagle-import:HEADER_MALE_01_NOBORDER")
      (fields (field (name "SPICEPREFIX") "X"))
      (libsource (lib "eagle-import") (part "HEADER/MALE/01NOBORDER"))
    )
    (comp (ref "P29")
      (value "HEADER/MALE/01NOBORDER")
      (footprint "eagle-import:HEADER_MALE_01_NOBORDER")
      (fields (field (name "SPICEPREFIX") "X"))
      (libsource (lib "eagle-import") (part "HEADER/MALE/01NOBORDER"))
    )
    (comp (ref "P30")
      (value "HEADER/MALE/01NOBORDER")
      (footprint "eagle-import:HEADER_MALE_01_NOBORDER")
      (fields (field (name "SPICEPREFIX") "X"))
      (libsource (lib "eagle-import") (part "HEADER/MALE/01NOBORDER"))
    )
    (comp (ref "P31")
      (value "HEADER/MALE/01NOBORDER")
      (footprint "eagle-import:HEADER_MALE_01_NOBORDER")
      (fields (field (name "SPICEPREFIX") "X"))
      (libsource (lib "eagle-import") (part "HEADER/MALE/01NOBORDER"))
    )
    (comp (ref "P32")
      (value "HEADER/MALE/01NOBORDER")
      (footprint "eagle-import:HEADER_MALE_01_NOBORDER")
      (fields (field (name "SPICEPREFIX") "X"))
      (libsource (lib "eagle-import") (part "HEADER/MALE/01NOBORDER"))
    )
    (comp (ref "P33")
      (value "HEADER/MALE/01NOBORDER")
      (footprint "eagle-import:HEADER_MALE_01_NOBORDER")
      (fields (field (name "SPICEPREFIX") "X"))
      (libsource (lib "eagle-import") (part "HEADER/MALE/01NOBORDER"))
    )
    (comp (ref "P34")
      (value "HEADER/MALE/01NOBORDER")
      (footprint "eagle-import:HEADER_MALE_01_NOBORDER")
      (fields (field (name "SPICEPREFIX") "X"))
      (libsource (lib "eagle-import") (part "HEADER/MALE/01NOBORDER"))
    )
    (comp (ref "P35")
      (value "HEADER/MALE/01NOBORDER")
      (footprint "eagle-import:HEADER_MALE_01_NOBORDER")
      (fields (field (name "SPICEPREFIX") "X"))
      (libsource (lib "eagle-import") (part "HEADER/MALE/01NOBORDER"))
    )
    (comp (ref "P36")
      (value "HEADER/MALE/01NOBORDER")
      (footprint "eagle-import:HEADER_MALE_01_NOBORDER")
      (fields (field (name "SPICEPREFIX") "X"))
      (libsource (lib "eagle-import") (part "HEADER/MALE/01NOBORDER"))
    )
    (comp (ref "P37")
      (value "HEADER/MALE/01NOBORDER")
      (footprint "eagle-import:HEADER_MALE_01_NOBORDER")
      (fields (field (name "SPICEPREFIX") "X"))
      (libsource (lib "eagle-import") (part "HEADER/MALE/01NOBORDER"))
    )
    (comp (ref "P38")
      (value "HEADER/MALE/01NOBORDER")
      (footprint "eagle-import:HEADER_MALE_01_NOBORDER")
      (fields (field (name "SPICEPREFIX") "X"))
      (libsource (lib "eagle-import") (part "HEADER/MALE/01NOBORDER"))
    )
    (comp (ref "P39")
      (value "HEADER/MALE/01NOBORDER")
      (footprint "eagle-import:HEADER_MALE_01_NOBORDER")
      (fields (field (name "SPICEPREFIX") "X"))
      (libsource (lib "eagle-import") (part "HEADER/MALE/01NOBORDER"))
    )
    (comp (ref "P40")
      (value "HEADER/MALE/01NOBORDER")
      (footprint "eagle-import:HEADER_MALE_01_NOBORDER")
      (fields (field (name "SPICEPREFIX") "X"))
      (libsource (lib "eagle-import") (part "HEADER/MALE/01NOBORDER"))
    )
    (comp (ref "P41")
      (value "HEADER/MALE/01NOBORDER")
      (footprint "eagle-import:HEADER_MALE_01_NOBORDER")
      (fields (field (name "SPICEPREFIX") "X"))
      (libsource (lib "eagle-import") (part "HEADER/MALE/01NOBORDER"))
    )
    (comp (ref "P42")
      (value "HEADER/MALE/01NOBORDER")
      (footprint "eagle-import:HEADER_MALE_01_NOBORDER")
      (fields (field (name "SPICEPREFIX") "X"))
      (libsource (lib "eagle-import") (part "HEADER/MALE/01NOBORDER"))
    )
    (comp (ref "P43")
      (value "HEADER/MALE/01NOBORDER")
      (footprint "eagle-import:HEADER_MALE_01_NOBORDER")
      (fields (field (name "SPICEPREFIX") "X"))
      (libsource (lib "eagle-import") (part "HEADER/MALE/01NOBORDER"))
    )
    (comp (ref "P44")
      (value "HEADER/MALE/01NOBORDER")
      (footprint "eagle-import:HEADER_MALE_01_NOBORDER")
      (fields (field (name "SPICEPREFIX") "X"))
      (libsource (lib "eagle-import") (part "HEADER/MALE/01NOBORDER"))
    )
    (comp (ref "P45")
      (value "HEADER/MALE/01NOBORDER")
      (footprint "eagle-import:HEADER_MALE_01_NOBORDER")
      (fields (field (name "SPICEPREFIX") "X"))
      (libsource (lib "eagle-import") (part "HEADER/MALE/01NOBORDER"))
    )
    (comp (ref "P46")
      (value "HEADER/MALE/01NOBORDER")
      (footprint "eagle-import:HEADER_MALE_01_NOBORDER")
      (fields (field (name "SPICEPREFIX") "X"))
      (libsource (lib "eagle-import") (part "HEADER/MALE/01NOBORDER"))
    )
    (comp (ref "P47")
      (value "HEADER/MALE/01NOBORDER")
      (footprint "eagle-import:HEADER_MALE_01_NOBORDER")
      (fields (field (name "SPICEPREFIX") "X"))
      (libsource (lib "eagle-import") (part "HEADER/MALE/01NOBORDER"))
    )
    (comp (ref "P48")
      (value "HEADER/MALE/01NOBORDER")
      (footprint "eagle-import:HEADER_MALE_01_NOBORDER")
      (fields (field (name "SPICEPREFIX") "X"))
      (libsource (lib "eagle-import") (part "HEADER/MALE/01NOBORDER"))
    )
    (comp (ref "P49")
      (value "HEADER/MALE/01NOBORDER")
      (footprint "eagle-import:HEADER_MALE_01_NOBORDER")
      (fields (field (name "SPICEPREFIX") "X"))
      (libsource (lib "eagle-import") (part "HEADER/MALE/01NOBORDER"))
    )
    (comp (ref "P50")
      (value "HEADER/MALE/01NOBORDER")
      (footprint "eagle-import:HEADER_MALE_01_NOBORDER")
      (fields (field (name "SPICEPREFIX") "X"))
      (libsource (lib "eagle-import") (part "HEADER/MALE/01NOBORDER"))
    )
    (comp (ref "Q1")
      (value "BF170")
      (footprint "eagle-import:SOT23")
      (libsource (lib "eagle-import") (part "BS170SOT23"))
    )
    (comp (ref "Q2")
      (value "BF170")
      (footprint "eagle-import:SOT23")
      (libsource (lib "eagle-import") (part "BS170SOT23"))
    )
    (comp (ref "Q3")
      (value "BF170")
      (footprint "eagle-import:SOT23")
      (libsource (lib "eagle-import") (part "BS170SOT23"))
    )
    (comp (ref "Q4")
      (value "BF170")
      (footprint "eagle-import:SOT23")
      (libsource (lib "eagle-import") (part "BS170SOT23"))
    )
    (comp (ref "Q5")
      (value "BF170")
      (footprint "eagle-import:SOT23")
      (libsource (lib "eagle-import") (part "BS170SOT23"))
    )
    (comp (ref "Q6")
      (value "BF170")
      (footprint "eagle-import:SOT23")
      (libsource (lib "eagle-import") (part "BS170SOT23"))
    )
    (comp (ref "Q7")
      (value "BF170")
      (footprint "eagle-import:SOT23")
      (libsource (lib "eagle-import") (part "BS170SOT23"))
    )
    (comp (ref "Q8")
      (value "BF170")
      (footprint "eagle-import:SOT23")
      (libsource (lib "eagle-import") (part "BS170SOT23"))
    )
    (comp (ref "Q9")
      (value "BF170")
      (footprint "eagle-import:SOT23")
      (libsource (lib "eagle-import") (part "BS170SOT23"))
    )
    (comp (ref "Q10")
      (value "BF170")
      (footprint "eagle-import:SOT23")
      (libsource (lib "eagle-import") (part "BS170SOT23"))
    )
    (comp (ref "Q11")
      (value "BF170")
      (footprint "eagle-import:SOT23")
      (libsource (lib "eagle-import") (part "BS170SOT23"))
    )
    (comp (ref "Q12")
      (value "BF170")
      (footprint "eagle-import:SOT23")
      (libsource (lib "eagle-import") (part "BS170SOT23"))
    )
    (comp (ref "Q13")
      (value "BF170")
      (footprint "eagle-import:SOT23")
      (libsource (lib "eagle-import") (part "BS170SOT23"))
    )
    (comp (ref "Q14")
      (value "BF170")
      (footprint "eagle-import:SOT23")
      (libsource (lib "eagle-import") (part "BS170SOT23"))
    )
    (comp (ref "Q15")
      (value "BF170")
      (footprint "eagle-import:SOT23")
      (libsource (lib "eagle-import") (part "BS170SOT23"))
    )
    (comp (ref "Q16")
      (value "BF170")
      (footprint "eagle-import:SOT23")
      (libsource (lib "eagle-import") (part "BS170SOT23"))
    )
    (comp (ref "R1")
      (value "120k")
      (footprint "eagle-import:R0603")
      (libsource (lib "eagle-import") (part "RESISTOR"))
    )
    (comp (ref "R2")
      (value "30k")
      (footprint "eagle-import:R0603")
      (libsource (lib "eagle-import") (part "RESISTOR"))
    )
    (comp (ref "R3")
      (value "1k")
      (footprint "eagle-import:R0603")
      (libsource (lib "eagle-import") (part "RESISTOR"))
    )
    (comp (ref "R4")
      (value "120k")
      (footprint "eagle-import:R0603")
      (libsource (lib "eagle-import") (part "RESISTOR"))
    )
    (comp (ref "R5")
      (value "30k")
      (footprint "eagle-import:R0603")
      (libsource (lib "eagle-import") (part "RESISTOR"))
    )
    (comp (ref "R6")
      (value "1k")
      (footprint "eagle-import:R0603")
      (libsource (lib "eagle-import") (part "RESISTOR"))
    )
    (comp (ref "R7")
      (value "2K")
      (footprint "eagle-import:R0603")
      (libsource (lib "eagle-import") (part "RESISTOR"))
    )
    (comp (ref "R8")
      (value "33k")
      (footprint "eagle-import:R0603")
      (libsource (lib "eagle-import") (part "RESISTOR"))
    )
    (comp (ref "R9")
      (value "120k")
      (footprint "eagle-import:R0603")
      (libsource (lib "eagle-import") (part "RESISTOR"))
    )
    (comp (ref "R10")
      (value "30k")
      (footprint "eagle-import:R0603")
      (libsource (lib "eagle-import") (part "RESISTOR"))
    )
    (comp (ref "R11")
      (value "100k")
      (footprint "eagle-import:R0603")
      (libsource (lib "eagle-import") (part "RESISTOR"))
    )
    (comp (ref "R12")
      (value "100k")
      (footprint "eagle-import:R0603")
      (libsource (lib "eagle-import") (part "RESISTOR"))
    )
    (comp (ref "R13")
      (value "100k")
      (footprint "eagle-import:R0603")
      (libsource (lib "eagle-import") (part "RESISTOR"))
    )
    (comp (ref "R14")
      (value "1k")
      (footprint "eagle-import:R0603")
      (libsource (lib "eagle-import") (part "RESISTOR"))
    )
    (comp (ref "R15")
      (value "33k")
      (footprint "eagle-import:R0603")
      (libsource (lib "eagle-import") (part "RESISTOR"))
    )
    (comp (ref "R16")
      (value "120k")
      (footprint "eagle-import:R0603")
      (libsource (lib "eagle-import") (part "RESISTOR"))
    )
    (comp (ref "R17")
      (value "30k")
      (footprint "eagle-import:R0603")
      (libsource (lib "eagle-import") (part "RESISTOR"))
    )
    (comp (ref "R18")
      (value "1k")
      (footprint "eagle-import:R0603")
      (libsource (lib "eagle-import") (part "RESISTOR"))
    )
    (comp (ref "R19")
      (value "120k")
      (footprint "eagle-import:R0603")
      (libsource (lib "eagle-import") (part "RESISTOR"))
    )
    (comp (ref "R20")
      (value "30k")
      (footprint "eagle-import:R0603")
      (libsource (lib "eagle-import") (part "RESISTOR"))
    )
    (comp (ref "R21")
      (value "33k")
      (footprint "eagle-import:R0603")
      (libsource (lib "eagle-import") (part "RESISTOR"))
    )
    (comp (ref "R22")
      (value "100k")
      (footprint "eagle-import:R0603")
      (libsource (lib "eagle-import") (part "RESISTOR"))
    )
    (comp (ref "R23")
      (value "100k")
      (footprint "eagle-import:R0603")
      (libsource (lib "eagle-import") (part "RESISTOR"))
    )
    (comp (ref "R24")
      (value "100k")
      (footprint "eagle-import:R0603")
      (libsource (lib "eagle-import") (part "RESISTOR"))
    )
    (comp (ref "R25")
      (value "33k")
      (footprint "eagle-import:R0603")
      (libsource (lib "eagle-import") (part "RESISTOR"))
    )
    (comp (ref "R26")
      (value "100k")
      (footprint "eagle-import:R0603")
      (libsource (lib "eagle-import") (part "RESISTOR"))
    )
    (comp (ref "R27")
      (value "100k")
      (footprint "eagle-import:R0603")
      (libsource (lib "eagle-import") (part "RESISTOR"))
    )
    (comp (ref "R28")
      (value "100k")
      (footprint "eagle-import:R0603")
      (libsource (lib "eagle-import") (part "RESISTOR"))
    )
    (comp (ref "R29")
      (value "100k")
      (footprint "eagle-import:R0603")
      (libsource (lib "eagle-import") (part "RESISTOR"))
    )
    (comp (ref "R30")
      (value "33k")
      (footprint "eagle-import:R0603")
      (libsource (lib "eagle-import") (part "RESISTOR"))
    )
    (comp (ref "R31")
      (value "100k")
      (footprint "eagle-import:R0603")
      (libsource (lib "eagle-import") (part "RESISTOR"))
    )
    (comp (ref "R32")
      (value "100k")
      (footprint "eagle-import:R0603")
      (libsource (lib "eagle-import") (part "RESISTOR"))
    )
    (comp (ref "R33")
      (value "100k")
      (footprint "eagle-import:R0603")
      (libsource (lib "eagle-import") (part "RESISTOR"))
    )
    (comp (ref "R34")
      (value "33k")
      (footprint "eagle-import:R0603")
      (libsource (lib "eagle-import") (part "RESISTOR"))
    )
    (comp (ref "R35")
      (value "100k")
      (footprint "eagle-import:R0603")
      (libsource (lib "eagle-import") (part "RESISTOR"))
    )
    (comp (ref "R36")
      (value "100k")
      (footprint "eagle-import:R0603")
      (libsource (lib "eagle-import") (part "RESISTOR"))
    )
    (comp (ref "R37")
      (value "100k")
      (footprint "eagle-import:R0603")
      (libsource (lib "eagle-import") (part "RESISTOR"))
    )
    (comp (ref "R38")
      (value "1k")
      (footprint "eagle-import:R0603")
      (libsource (lib "eagle-import") (part "RESISTOR"))
    )
    (comp (ref "R39")
      (value "120k")
      (footprint "eagle-import:R0603")
      (libsource (lib "eagle-import") (part "RESISTOR"))
    )
    (comp (ref "R40")
      (value "30k")
      (footprint "eagle-import:R0603")
      (libsource (lib "eagle-import") (part "RESISTOR"))
    )
    (comp (ref "R41")
      (value "1k")
      (footprint "eagle-import:R0603")
      (libsource (lib "eagle-import") (part "RESISTOR"))
    )
    (comp (ref "R42")
      (value "120k")
      (footprint "eagle-import:R0603")
      (libsource (lib "eagle-import") (part "RESISTOR"))
    )
    (comp (ref "R43")
      (value "30k")
      (footprint "eagle-import:R0603")
      (libsource (lib "eagle-import") (part "RESISTOR"))
    )
    (comp (ref "R44")
      (value "1k")
      (footprint "eagle-import:R0603")
      (libsource (lib "eagle-import") (part "RESISTOR"))
    )
    (comp (ref "R45")
      (value "120k")
      (footprint "eagle-import:R0603")
      (libsource (lib "eagle-import") (part "RESISTOR"))
    )
    (comp (ref "R46")
      (value "30k")
      (footprint "eagle-import:R0603")
      (libsource (lib "eagle-import") (part "RESISTOR"))
    )
    (comp (ref "R47")
      (value "1k")
      (footprint "eagle-import:R0603")
      (libsource (lib "eagle-import") (part "RESISTOR"))
    )
    (comp (ref "R48")
      (value "120k")
      (footprint "eagle-import:R0603")
      (libsource (lib "eagle-import") (part "RESISTOR"))
    )
    (comp (ref "R49")
      (value "120k")
      (footprint "eagle-import:R0603")
      (libsource (lib "eagle-import") (part "RESISTOR"))
    )
    (comp (ref "R50")
      (value "120k")
      (footprint "eagle-import:R0603")
      (libsource (lib "eagle-import") (part "RESISTOR"))
    )
    (comp (ref "R51")
      (value "120k")
      (footprint "eagle-import:R0603")
      (libsource (lib "eagle-import") (part "RESISTOR"))
    )
    (comp (ref "R52")
      (value "120k")
      (footprint "eagle-import:R0603")
      (libsource (lib "eagle-import") (part "RESISTOR"))
    )
    (comp (ref "R53")
      (value "120k")
      (footprint "eagle-import:R0603")
      (libsource (lib "eagle-import") (part "RESISTOR"))
    )
    (comp (ref "R54")
      (value "120k")
      (footprint "eagle-import:R0603")
      (libsource (lib "eagle-import") (part "RESISTOR"))
    )
    (comp (ref "R55")
      (value "120k")
      (footprint "eagle-import:R0603")
      (libsource (lib "eagle-import") (part "RESISTOR"))
    )
    (comp (ref "R56")
      (value "10k")
      (footprint "eagle-import:R0603")
      (libsource (lib "eagle-import") (part "RESISTOR"))
    )
    (comp (ref "R57")
      (value "10k")
      (footprint "eagle-import:R0603")
      (libsource (lib "eagle-import") (part "RESISTOR"))
    )
    (comp (ref "R58")
      (value "10k")
      (footprint "eagle-import:R0603")
      (libsource (lib "eagle-import") (part "RESISTOR"))
    )
    (comp (ref "R59")
      (value "10k")
      (footprint "eagle-import:R0603")
      (libsource (lib "eagle-import") (part "RESISTOR"))
    )
    (comp (ref "R60")
      (value "10k")
      (footprint "eagle-import:R0603")
      (libsource (lib "eagle-import") (part "RESISTOR"))
    )
    (comp (ref "R61")
      (value "10k")
      (footprint "eagle-import:R0603")
      (libsource (lib "eagle-import") (part "RESISTOR"))
    )
    (comp (ref "R62")
      (value "100k")
      (footprint "eagle-import:R0603")
      (libsource (lib "eagle-import") (part "RESISTOR"))
    )
    (comp (ref "R63")
      (value "100k")
      (footprint "eagle-import:R0603")
      (libsource (lib "eagle-import") (part "RESISTOR"))
    )
    (comp (ref "R64")
      (value "33k")
      (footprint "eagle-import:R0603")
      (libsource (lib "eagle-import") (part "RESISTOR"))
    )
    (comp (ref "R65")
      (value "100k")
      (footprint "eagle-import:R0603")
      (libsource (lib "eagle-import") (part "RESISTOR"))
    )
    (comp (ref "R66")
      (value "100k")
      (footprint "eagle-import:R0603")
      (libsource (lib "eagle-import") (part "RESISTOR"))
    )
    (comp (ref "R67")
      (value "100k")
      (footprint "eagle-import:R0603")
      (libsource (lib "eagle-import") (part "RESISTOR"))
    )
    (comp (ref "R68")
      (value "33k")
      (footprint "eagle-import:R0603")
      (libsource (lib "eagle-import") (part "RESISTOR"))
    )
    (comp (ref "R69")
      (value "100k")
      (footprint "eagle-import:R0603")
      (libsource (lib "eagle-import") (part "RESISTOR"))
    )
    (comp (ref "R70")
      (value "100k")
      (footprint "eagle-import:R0603")
      (libsource (lib "eagle-import") (part "RESISTOR"))
    )
    (comp (ref "R71")
      (value "100k")
      (footprint "eagle-import:R0603")
      (libsource (lib "eagle-import") (part "RESISTOR"))
    )
    (comp (ref "R72")
      (value "10k")
      (footprint "eagle-import:R0603")
      (libsource (lib "eagle-import") (part "RESISTOR"))
    )
    (comp (ref "R73")
      (value "10k")
      (footprint "eagle-import:R0603")
      (libsource (lib "eagle-import") (part "RESISTOR"))
    )
    (comp (ref "R74")
      (value "10k")
      (footprint "eagle-import:R0603")
      (libsource (lib "eagle-import") (part "RESISTOR"))
    )
    (comp (ref "R75")
      (value "10k")
      (footprint "eagle-import:R0603")
      (libsource (lib "eagle-import") (part "RESISTOR"))
    )
    (comp (ref "R76")
      (value "10k")
      (footprint "eagle-import:R0603")
      (libsource (lib "eagle-import") (part "RESISTOR"))
    )
    (comp (ref "R77")
      (value "10k")
      (footprint "eagle-import:R0603")
      (libsource (lib "eagle-import") (part "RESISTOR"))
    )
    (comp (ref "R78")
      (value "10k")
      (footprint "eagle-import:R0603")
      (libsource (lib "eagle-import") (part "RESISTOR"))
    )
    (comp (ref "R79")
      (value "10k")
      (footprint "eagle-import:R0603")
      (libsource (lib "eagle-import") (part "RESISTOR"))
    )
    (comp (ref "R80")
      (value "10k")
      (footprint "eagle-import:R0603")
      (libsource (lib "eagle-import") (part "RESISTOR"))
    )
    (comp (ref "R81")
      (value "10k")
      (footprint "eagle-import:R0603")
      (libsource (lib "eagle-import") (part "RESISTOR"))
    )
    (comp (ref "R82")
      (value "1k")
      (footprint "eagle-import:R0603")
      (libsource (lib "eagle-import") (part "RESISTOR"))
    )
    (comp (ref "R83")
      (value "33k")
      (footprint "eagle-import:R0603")
      (libsource (lib "eagle-import") (part "RESISTOR"))
    )
    (comp (ref "R84")
      (value "100k")
      (footprint "eagle-import:R0603")
      (libsource (lib "eagle-import") (part "RESISTOR"))
    )
    (comp (ref "R85")
      (value "100k")
      (footprint "eagle-import:R0603")
      (libsource (lib "eagle-import") (part "RESISTOR"))
    )
    (comp (ref "R86")
      (value "100k")
      (footprint "eagle-import:R0603")
      (libsource (lib "eagle-import") (part "RESISTOR"))
    )
    (comp (ref "R87")
      (value "33k")
      (footprint "eagle-import:R0603")
      (libsource (lib "eagle-import") (part "RESISTOR"))
    )
    (comp (ref "R88")
      (value "100k")
      (footprint "eagle-import:R0603")
      (libsource (lib "eagle-import") (part "RESISTOR"))
    )
    (comp (ref "R89")
      (value "100k")
      (footprint "eagle-import:R0603")
      (libsource (lib "eagle-import") (part "RESISTOR"))
    )
    (comp (ref "R90")
      (value "100k")
      (footprint "eagle-import:R0603")
      (libsource (lib "eagle-import") (part "RESISTOR"))
    )
    (comp (ref "R91")
      (value "33k")
      (footprint "eagle-import:R0603")
      (libsource (lib "eagle-import") (part "RESISTOR"))
    )
    (comp (ref "R92")
      (value "100k")
      (footprint "eagle-import:R0603")
      (libsource (lib "eagle-import") (part "RESISTOR"))
    )
    (comp (ref "R93")
      (value "100k")
      (footprint "eagle-import:R0603")
      (libsource (lib "eagle-import") (part "RESISTOR"))
    )
    (comp (ref "R94")
      (value "100k")
      (footprint "eagle-import:R0603")
      (libsource (lib "eagle-import") (part "RESISTOR"))
    )
    (comp (ref "R95")
      (value "33k")
      (footprint "eagle-import:R0603")
      (libsource (lib "eagle-import") (part "RESISTOR"))
    )
    (comp (ref "R96")
      (value "100k")
      (footprint "eagle-import:R0603")
      (libsource (lib "eagle-import") (part "RESISTOR"))
    )
    (comp (ref "R97")
      (value "100k")
      (footprint "eagle-import:R0603")
      (libsource (lib "eagle-import") (part "RESISTOR"))
    )
    (comp (ref "R98")
      (value "100k")
      (footprint "eagle-import:R0603")
      (libsource (lib "eagle-import") (part "RESISTOR"))
    )
    (comp (ref "R99")
      (value "10k")
      (footprint "eagle-import:R0603")
      (libsource (lib "eagle-import") (part "RESISTOR"))
    )
    (comp (ref "R100")
      (value "10k")
      (footprint "eagle-import:R0603")
      (libsource (lib "eagle-import") (part "RESISTOR"))
    )
    (comp (ref "R101")
      (value "10k")
      (footprint "eagle-import:R0603")
      (libsource (lib "eagle-import") (part "RESISTOR"))
    )
    (comp (ref "R102")
      (value "10k")
      (footprint "eagle-import:R0603")
      (libsource (lib "eagle-import") (part "RESISTOR"))
    )
    (comp (ref "R103")
      (value "10k")
      (footprint "eagle-import:R0603")
      (libsource (lib "eagle-import") (part "RESISTOR"))
    )
    (comp (ref "R104")
      (value "10k")
      (footprint "eagle-import:R0603")
      (libsource (lib "eagle-import") (part "RESISTOR"))
    )
    (comp (ref "R105")
      (value "10k")
      (footprint "eagle-import:R0603")
      (libsource (lib "eagle-import") (part "RESISTOR"))
    )
    (comp (ref "R106")
      (value "10k")
      (footprint "eagle-import:R0603")
      (libsource (lib "eagle-import") (part "RESISTOR"))
    )
    (comp (ref "R107")
      (value "10k")
      (footprint "eagle-import:R0603")
      (libsource (lib "eagle-import") (part "RESISTOR"))
    )
    (comp (ref "R108")
      (value "10k")
      (footprint "eagle-import:R0603")
      (libsource (lib "eagle-import") (part "RESISTOR"))
    )
    (comp (ref "R109")
      (value "10k")
      (footprint "eagle-import:R0603")
      (libsource (lib "eagle-import") (part "RESISTOR"))
    )
    (comp (ref "R110")
      (value "10k")
      (footprint "eagle-import:R0603")
      (libsource (lib "eagle-import") (part "RESISTOR"))
    )
    (comp (ref "R111")
      (value "10k")
      (footprint "eagle-import:R0603")
      (libsource (lib "eagle-import") (part "RESISTOR"))
    )
    (comp (ref "R112")
      (value "10k")
      (footprint "eagle-import:R0603")
      (libsource (lib "eagle-import") (part "RESISTOR"))
    )
    (comp (ref "R113")
      (value "10k")
      (footprint "eagle-import:R0603")
      (libsource (lib "eagle-import") (part "RESISTOR"))
    )
    (comp (ref "R114")
      (value "10k")
      (footprint "eagle-import:R0603")
      (libsource (lib "eagle-import") (part "RESISTOR"))
    )
    (comp (ref "R115")
      (value "2K")
      (footprint "eagle-import:R0603")
      (libsource (lib "eagle-import") (part "RESISTOR"))
    )
    (comp (ref "R116")
      (value "2K")
      (footprint "eagle-import:R0603")
      (libsource (lib "eagle-import") (part "RESISTOR"))
    )
  )
  (nets
    (net (code "1") (name "+12V") (class "Default")
      (node (ref "+V") (pin "1") (pinfunction "3_1") (pintype "passive"))
      (node (ref "+V1") (pin "1") (pinfunction "3_1") (pintype "passive"))
      (node (ref "+V2") (pin "1") (pinfunction "3_1") (pintype "passive"))
      (node (ref "+V3") (pin "1") (pinfunction "3_1") (pintype "passive"))
      (node (ref "+V4") (pin "1") (pinfunction "3_1") (pintype "passive"))
      (node (ref "+V5") (pin "1") (pinfunction "3_1") (pintype "passive"))
      (node (ref "C1") (pin "+") (pinfunction "+_+") (pintype "passive"))
      (node (ref "C23") (pin "2") (pinfunction "2_2") (pintype "passive"))
      (node (ref "C26") (pin "2") (pinfunction "2_2") (pintype "passive"))
      (node (ref "IC1") (pin "4") (pinfunction "V+_4") (pintype "power_in"))
      (node (ref "IC5") (pin "4") (pinfunction "V+_4") (pintype "power_in"))
      (node (ref "L1") (pin "1") (pinfunction "1_1") (pintype "passive"))
    )
    (net (code "2") (name "-12V") (class "Default")
      (node (ref "-V") (pin "1") (pinfunction "3_1") (pintype "passive"))
      (node (ref "-V1") (pin "1") (pinfunction "3_1") (pintype "passive"))
      (node (ref "-V2") (pin "1") (pinfunction "3_1") (pintype "passive"))
      (node (ref "-V3") (pin "1") (pinfunction "3_1") (pintype "passive"))
      (node (ref "-V4") (pin "1") (pinfunction "3_1") (pintype "passive"))
      (node (ref "-V5") (pin "1") (pinfunction "3_1") (pintype "passive"))
      (node (ref "C2") (pin "-") (pinfunction "-_-") (pintype "passive"))
      (node (ref "C24") (pin "1") (pinfunction "1_1") (pintype "passive"))
      (node (ref "C25") (pin "1") (pinfunction "1_1") (pintype "passive"))
      (node (ref "IC1") (pin "11") (pinfunction "V-_11") (pintype "power_in"))
      (node (ref "IC5") (pin "11") (pinfunction "V-_11") (pintype "power_in"))
      (node (ref "R7") (pin "2") (pinfunction "2_2") (pintype "passive"))
    )
    (net (code "3") (name "/-5VREF") (class "Default")
      (node (ref "-5V") (pin "1") (pinfunction "3_1") (pintype "passive"))
      (node (ref "-5V1") (pin "1") (pinfunction "3_1") (pintype "passive"))
      (node (ref "-5V2") (pin "1") (pinfunction "3_1") (pintype "passive"))
      (node (ref "-5V3") (pin "1") (pinfunction "3_1") (pintype "passive"))
      (node (ref "C6") (pin "2") (pinfunction "2_2") (pintype "passive"))
      (node (ref "IC8") (pin "2") (pinfunction "A_2") (pintype "output"))
      (node (ref "R13") (pin "1") (pinfunction "1_1") (pintype "passive"))
      (node (ref "R24") (pin "1") (pinfunction "1_1") (pintype "passive"))
      (node (ref "R26") (pin "1") (pinfunction "1_1") (pintype "passive"))
      (node (ref "R29") (pin "1") (pinfunction "1_1") (pintype "passive"))
      (node (ref "R33") (pin "1") (pinfunction "1_1") (pintype "passive"))
      (node (ref "R37") (pin "1") (pinfunction "1_1") (pintype "passive"))
      (node (ref "R48") (pin "1") (pinfunction "1_1") (pintype "passive"))
      (node (ref "R49") (pin "1") (pinfunction "1_1") (pintype "passive"))
      (node (ref "R50") (pin "1") (pinfunction "1_1") (pintype "passive"))
      (node (ref "R51") (pin "1") (pinfunction "1_1") (pintype "passive"))
      (node (ref "R52") (pin "1") (pinfunction "1_1") (pintype "passive"))
      (node (ref "R53") (pin "1") (pinfunction "1_1") (pintype "passive"))
      (node (ref "R54") (pin "1") (pinfunction "1_1") (pintype "passive"))
      (node (ref "R55") (pin "1") (pinfunction "1_1") (pintype "passive"))
      (node (ref "R67") (pin "1") (pinfunction "1_1") (pintype "passive"))
      (node (ref "R7") (pin "1") (pinfunction "1_1") (pintype "passive"))
      (node (ref "R71") (pin "1") (pinfunction "1_1") (pintype "passive"))
      (node (ref "R86") (pin "1") (pinfunction "1_1") (pintype "passive"))
      (node (ref "R88") (pin "1") (pinfunction "1_1") (pintype "passive"))
      (node (ref "R94") (pin "1") (pinfunction "1_1") (pintype "passive"))
      (node (ref "R98") (pin "1") (pinfunction "1_1") (pintype "passive"))
    )
    (net (code "4") (name "/3.3V") (class "Default")
      (node (ref "3.3V") (pin "1") (pinfunction "3_1") (pintype "passive"))
      (node (ref "3.3V1") (pin "1") (pinfunction "3_1") (pintype "passive"))
      (node (ref "3.3V2") (pin "1") (pinfunction "3_1") (pintype "passive"))
      (node (ref "3.3V3") (pin "1") (pinfunction "3_1") (pintype "passive"))
      (node (ref "C15") (pin "2") (pinfunction "2_2") (pintype "passive"))
      (node (ref "C18") (pin "2") (pinfunction "2_2") (pintype "passive"))
      (node (ref "C32") (pin "2") (pinfunction "2_2") (pintype "passive"))
      (node (ref "IC10") (pin "12") (pinfunction "IOVDD_12") (pintype "power_in"))
      (node (ref "IC10") (pin "4") (pinfunction "AVDD_4") (pintype "power_in"))
      (node (ref "IC11") (pin "12") (pinfunction "IOVDD_12") (pintype "power_in"))
      (node (ref "IC11") (pin "4") (pinfunction "AVDD_4") (pintype "power_in"))
      (node (ref "IC2") (pin "9") (pinfunction "VDD_9") (pintype "power_in"))
      (node (ref "IC3") (pin "4") (pinfunction "V+_4") (pintype "power_in"))
      (node (ref "IC4") (pin "4") (pinfunction "V+_4") (pintype "power_in"))
      (node (ref "IC6") (pin "3V3-3") (pinfunction "3V3-3_3V3-3") (pintype "bidirectional"))
      (node (ref "IC9") (pin "4") (pinfunction "V+_4") (pintype "power_in"))
      (node (ref "Q1") (pin "1") (pinfunction "G_1") (pintype "passive"))
      (node (ref "Q10") (pin "1") (pinfunction "G_1") (pintype "passive"))
      (node (ref "Q11") (pin "1") (pinfunction "G_1") (pintype "passive"))
      (node (ref "Q12") (pin "1") (pinfunction "G_1") (pintype "passive"))
      (node (ref "Q13") (pin "1") (pinfunction "G_1") (pintype "passive"))
      (node (ref "Q14") (pin "1") (pinfunction "G_1") (pintype "passive"))
      (node (ref "Q15") (pin "1") (pinfunction "G_1") (pintype "passive"))
      (node (ref "Q16") (pin "1") (pinfunction "G_1") (pintype "passive"))
      (node (ref "Q2") (pin "1") (pinfunction "G_1") (pintype "passive"))
      (node (ref "Q3") (pin "1") (pinfunction "G_1") (pintype "passive"))
      (node (ref "Q4") (pin "1") (pinfunction "G_1") (pintype "passive"))
      (node (ref "Q5") (pin "1") (pinfunction "G_1") (pintype "passive"))
      (node (ref "Q6") (pin "1") (pinfunction "G_1") (pintype "passive"))
      (node (ref "Q7") (pin "1") (pinfunction "G_1") (pintype "passive"))
      (node (ref "Q8") (pin "1") (pinfunction "G_1") (pintype "passive"))
      (node (ref "Q9") (pin "1") (pinfunction "G_1") (pintype "passive"))
      (node (ref "R101") (pin "2") (pinfunction "2_2") (pintype "passive"))
      (node (ref "R103") (pin "2") (pinfunction "2_2") (pintype "passive"))
      (node (ref "R105") (pin "2") (pinfunction "2_2") (pintype "passive"))
      (node (ref "R107") (pin "2") (pinfunction "2_2") (pintype "passive"))
      (node (ref "R109") (pin "2") (pinfunction "2_2") (pintype "passive"))
      (node (ref "R111") (pin "2") (pinfunction "2_2") (pintype "passive"))
      (node (ref "R113") (pin "2") (pinfunction "2_2") (pintype "passive"))
      (node (ref "R115") (pin "2") (pinfunction "2_2") (pintype "passive"))
      (node (ref "R116") (pin "2") (pinfunction "2_2") (pintype "passive"))
      (node (ref "R56") (pin "2") (pinfunction "2_2") (pintype "passive"))
      (node (ref "R57") (pin "2") (pinfunction "2_2") (pintype "passive"))
      (node (ref "R59") (pin "2") (pinfunction "2_2") (pintype "passive"))
      (node (ref "R61") (pin "2") (pinfunction "2_2") (pintype "passive"))
      (node (ref "R73") (pin "2") (pinfunction "2_2") (pintype "passive"))
      (node (ref "R75") (pin "2") (pinfunction "2_2") (pintype "passive"))
      (node (ref "R77") (pin "2") (pinfunction "2_2") (pintype "passive"))
      (node (ref "R79") (pin "2") (pinfunction "2_2") (pintype "passive"))
      (node (ref "R81") (pin "2") (pinfunction "2_2") (pintype "passive"))
      (node (ref "R82") (pin "1") (pinfunction "1_1") (pintype "passive"))
    )
    (net (code "5") (name "/ADC0") (class "Default")
      (node (ref "C7") (pin "2") (pinfunction "2_2") (pintype "passive"))
      (node (ref "IC3") (pin "1") (pinfunction "OUT_1") (pintype "output"))
      (node (ref "IC6") (pin "14-A0/TX3/SPDIF_OUT") (pinfunction "14-A0/TX3/SPDIF_OUT_14-A0/TX3/SPDIF_OUT") (pintype "bidirectional"))
      (node (ref "R8") (pin "2") (pinfunction "2_2") (pintype "passive"))
    )
    (net (code "6") (name "/ADC1") (class "Default")
      (node (ref "C14") (pin "2") (pinfunction "2_2") (pintype "passive"))
      (node (ref "IC3") (pin "14") (pinfunction "OUT_14") (pintype "output"))
      (node (ref "IC6") (pin "15-A1/RX3/SPDIF_IN") (pinfunction "15-A1/RX3/SPDIF_IN_15-A1/RX3/SPDIF_IN") (pintype "bidirectional"))
      (node (ref "R68") (pin "2") (pinfunction "2_2") (pintype "passive"))
    )
    (net (code "7") (name "/ADC2") (class "Default")
      (node (ref "C10") (pin "2") (pinfunction "2_2") (pintype "passive"))
      (node (ref "IC3") (pin "7") (pinfunction "OUT_7") (pintype "output"))
      (node (ref "IC6") (pin "16-A2/RX4/SCL1") (pinfunction "16-A2/RX4/SCL1_16-A2/RX4/SCL1") (pintype "bidirectional"))
      (node (ref "R15") (pin "2") (pinfunction "2_2") (pintype "passive"))
    )
    (net (code "8") (name "/ADC3") (class "Default")
      (node (ref "C11") (pin "2") (pinfunction "2_2") (pintype "passive"))
      (node (ref "IC3") (pin "8") (pinfunction "OUT_8") (pintype "output"))
      (node (ref "IC6") (pin "17-A3/TX4/SDA1") (pinfunction "17-A3/TX4/SDA1_17-A3/TX4/SDA1") (pintype "bidirectional"))
      (node (ref "R64") (pin "2") (pinfunction "2_2") (pintype "passive"))
    )
    (net (code "9") (name "/ADC4") (class "Default")
      (node (ref "C16") (pin "2") (pinfunction "2_2") (pintype "passive"))
      (node (ref "IC4") (pin "1") (pinfunction "OUT_1") (pintype "output"))
      (node (ref "IC6") (pin "20-A6/TX5/LRCLK1") (pinfunction "20-A6/TX5/LRCLK1_20-A6/TX5/LRCLK1") (pintype "bidirectional"))
      (node (ref "R21") (pin "2") (pinfunction "2_2") (pintype "passive"))
    )
    (net (code "10") (name "/ADC5") (class "Default")
      (node (ref "C21") (pin "2") (pinfunction "2_2") (pintype "passive"))
      (node (ref "IC4") (pin "14") (pinfunction "OUT_14") (pintype "output"))
      (node (ref "IC6") (pin "21-A7/RX5/BCLK1") (pinfunction "21-A7/RX5/BCLK1_21-A7/RX5/BCLK1") (pintype "bidirectional"))
      (node (ref "R34") (pin "2") (pinfunction "2_2") (pintype "passive"))
    )
    (net (code "11") (name "/ADC6") (class "Default")
      (node (ref "C17") (pin "2") (pinfunction "2_2") (pintype "passive"))
      (node (ref "IC4") (pin "7") (pinfunction "OUT_7") (pintype "output"))
      (node (ref "IC6") (pin "22-A8/CTX1") (pinfunction "22-A8/CTX1_22-A8/CTX1") (pintype "bidirectional"))
      (node (ref "R25") (pin "2") (pinfunction "2_2") (pintype "passive"))
    )
    (net (code "12") (name "/ADC7") (class "Default")
      (node (ref "C20") (pin "2") (pinfunction "2_2") (pintype "passive"))
      (node (ref "IC4") (pin "8") (pinfunction "OUT_8") (pintype "output"))
      (node (ref "IC6") (pin "23-A9/CRX1/MCLK1") (pinfunction "23-A9/CRX1/MCLK1_23-A9/CRX1/MCLK1") (pintype "bidirectional"))
      (node (ref "R30") (pin "2") (pinfunction "2_2") (pintype "passive"))
    )
    (net (code "13") (name "/ADC8") (class "Default")
      (node (ref "24_4.0-A10") (pin "1") (pinfunction "3_1") (pintype "passive"))
      (node (ref "24_LC-A10") (pin "1") (pinfunction "3_1") (pintype "passive"))
      (node (ref "C30") (pin "2") (pinfunction "2_2") (pintype "passive"))
      (node (ref "IC6") (pin "24-A10/TX6/SCL2") (pinfunction "24-A10/TX6/SCL2_24-A10/TX6/SCL2") (pintype "bidirectional"))
      (node (ref "IC9") (pin "8") (pinfunction "OUT_8") (pintype "output"))
      (node (ref "R91") (pin "2") (pinfunction "2_2") (pintype "passive"))
    )
    (net (code "14") (name "/ADC9") (class "Default")
      (node (ref "25_4.0-A11") (pin "1") (pinfunction "3_1") (pintype "passive"))
      (node (ref "25_LC-A11") (pin "1") (pinfunction "3_1") (pintype "passive"))
      (node (ref "C29") (pin "2") (pinfunction "2_2") (pintype "passive"))
      (node (ref "IC6") (pin "25-A11/RX6/SDA2") (pinfunction "25-A11/RX6/SDA2_25-A11/RX6/SDA2") (pintype "bidirectional"))
      (node (ref "IC9") (pin "7") (pinfunction "OUT_7") (pintype "output"))
      (node (ref "R87") (pin "2") (pinfunction "2_2") (pintype "passive"))
    )
    (net (code "15") (name "/ADC10") (class "Default")
      (node (ref "26_4.0-A12") (pin "1") (pinfunction "3_1") (pintype "passive"))
      (node (ref "26_LC-A12") (pin "1") (pinfunction "3_1") (pintype "passive"))
      (node (ref "C31") (pin "2") (pinfunction "2_2") (pintype "passive"))
      (node (ref "IC6") (pin "26-A12/MOSI1") (pinfunction "26-A12/MOSI1_26-A12/MOSI1") (pintype "bidirectional"))
      (node (ref "IC9") (pin "14") (pinfunction "OUT_14") (pintype "output"))
      (node (ref "R95") (pin "2") (pinfunction "2_2") (pintype "passive"))
    )
    (net (code "16") (name "/ADC11") (class "Default")
      (node (ref "27_4.0-A13") (pin "1") (pinfunction "3_1") (pintype "passive"))
      (node (ref "C28") (pin "2") (pinfunction "2_2") (pintype "passive"))
      (node (ref "IC6") (pin "27-A13/SCK1") (pinfunction "27-A13/SCK1_27-A13/SCK1") (pintype "bidirectional"))
      (node (ref "IC9") (pin "1") (pinfunction "OUT_1") (pintype "output"))
      (node (ref "R83") (pin "2") (pinfunction "2_2") (pintype "passive"))
    )
    (net (code "17") (name "/DAC1") (class "Default")
      (node (ref "DAC1") (pin "1") (pinfunction "3_1") (pintype "passive"))
      (node (ref "IC11") (pin "7") (pinfunction "VOUTC_7") (pintype "tri_state"))
      (node (ref "R46") (pin "1") (pinfunction "1_1") (pintype "passive"))
    )
    (net (code "18") (name "/DAC2") (class "Default")
      (node (ref "DAC2") (pin "1") (pinfunction "3_1") (pintype "passive"))
      (node (ref "IC11") (pin "2") (pinfunction "VOUTB_2") (pintype "tri_state"))
      (node (ref "R20") (pin "1") (pinfunction "1_1") (pintype "passive"))
    )
    (net (code "19") (name "/DAC3") (class "Default")
      (node (ref "DAC4") (pin "1") (pinfunction "3_1") (pintype "passive"))
      (node (ref "IC11") (pin "8") (pinfunction "VOUTD_8") (pintype "tri_state"))
      (node (ref "R43") (pin "1") (pinfunction "1_1") (pintype "passive"))
    )
    (net (code "20") (name "/DAC4") (class "Default")
      (node (ref "DAC3") (pin "1") (pinfunction "3_1") (pintype "passive"))
      (node (ref "IC11") (pin "1") (pinfunction "VOUTA_1") (pintype "tri_state"))
      (node (ref "R40") (pin "1") (pinfunction "1_1") (pintype "passive"))
    )
    (net (code "21") (name "/DAC5") (class "Default")
      (node (ref "IC10") (pin "1") (pinfunction "VOUTA_1") (pintype "tri_state"))
      (node (ref "R17") (pin "1") (pinfunction "1_1") (pintype "passive"))
    )
    (net (code "22") (name "/DAC6") (class "Default")
      (node (ref "IC10") (pin "8") (pinfunction "VOUTD_8") (pintype "tri_state"))
      (node (ref "R2") (pin "1") (pinfunction "1_1") (pintype "passive"))
    )
    (net (code "23") (name "/DAC7") (class "Default")
      (node (ref "IC10") (pin "2") (pinfunction "VOUTB_2") (pintype "tri_state"))
      (node (ref "R10") (pin "1") (pinfunction "1_1") (pintype "passive"))
    )
    (net (code "24") (name "/DAC8") (class "Default")
      (node (ref "IC10") (pin "7") (pinfunction "VOUTC_7") (pintype "tri_state"))
      (node (ref "R5") (pin "1") (pinfunction "1_1") (pintype "passive"))
    )
    (net (code "25") (name "/GPA0") (class "Default")
      (node (ref "IC2") (pin "21") (pinfunction "GPA0_21") (pintype "bidirectional"))
      (node (ref "Q1") (pin "2") (pinfunction "S_2") (pintype "passive"))
      (node (ref "R56") (pin "1") (pinfunction "1_1") (pintype "passive"))
    )
    (net (code "26") (name "/GPA1") (class "Default")
      (node (ref "IC2") (pin "22") (pinfunction "GPA1_22") (pintype "bidirectional"))
      (node (ref "Q2") (pin "2") (pinfunction "S_2") (pintype "passive"))
      (node (ref "R57") (pin "1") (pinfunction "1_1") (pintype "passive"))
    )
    (net (code "27") (name "/GPA2") (class "Default")
      (node (ref "IC2") (pin "23") (pinfunction "GPA2_23") (pintype "bidirectional"))
      (node (ref "Q3") (pin "2") (pinfunction "S_2") (pintype "passive"))
      (node (ref "R59") (pin "1") (pinfunction "1_1") (pintype "passive"))
    )
    (net (code "28") (name "/GPA3") (class "Default")
      (node (ref "IC2") (pin "24") (pinfunction "GPA3_24") (pintype "bidirectional"))
      (node (ref "Q4") (pin "2") (pinfunction "S_2") (pintype "passive"))
      (node (ref "R61") (pin "1") (pinfunction "1_1") (pintype "passive"))
    )
    (net (code "29") (name "/GPA4") (class "Default")
      (node (ref "IC2") (pin "25") (pinfunction "GPA4_25") (pintype "bidirectional"))
      (node (ref "Q5") (pin "2") (pinfunction "S_2") (pintype "passive"))
      (node (ref "R73") (pin "1") (pinfunction "1_1") (pintype "passive"))
    )
    (net (code "30") (name "/GPA5") (class "Default")
      (node (ref "IC2") (pin "26") (pinfunction "GPA5_26") (pintype "bidirectional"))
      (node (ref "Q6") (pin "2") (pinfunction "S_2") (pintype "passive"))
      (node (ref "R75") (pin "1") (pinfunction "1_1") (pintype "passive"))
    )
    (net (code "31") (name "/GPA6") (class "Default")
      (node (ref "IC2") (pin "27") (pinfunction "GPA6_27") (pintype "bidirectional"))
      (node (ref "Q7") (pin "2") (pinfunction "S_2") (pintype "passive"))
      (node (ref "R77") (pin "1") (pinfunction "1_1") (pintype "passive"))
    )
    (net (code "32") (name "/GPA7") (class "Default")
      (node (ref "IC2") (pin "28") (pinfunction "GPA7_28") (pintype "bidirectional"))
      (node (ref "Q8") (pin "2") (pinfunction "S_2") (pintype "passive"))
      (node (ref "R79") (pin "1") (pinfunction "1_1") (pintype "passive"))
    )
    (net (code "33") (name "/GPB0") (class "Default")
      (node (ref "IC2") (pin "1") (pinfunction "GPB0_1") (pintype "bidirectional"))
      (node (ref "Q9") (pin "2") (pinfunction "S_2") (pintype "passive"))
      (node (ref "R81") (pin "1") (pinfunction "1_1") (pintype "passive"))
    )
    (net (code "34") (name "/GPB1") (class "Default")
      (node (ref "IC2") (pin "2") (pinfunction "GPB1_2") (pintype "bidirectional"))
      (node (ref "Q10") (pin "2") (pinfunction "S_2") (pintype "passive"))
      (node (ref "R101") (pin "1") (pinfunction "1_1") (pintype "passive"))
    )
    (net (code "35") (name "/GPB2") (class "Default")
      (node (ref "IC2") (pin "3") (pinfunction "GPB2_3") (pintype "bidirectional"))
      (node (ref "Q11") (pin "2") (pinfunction "S_2") (pintype "passive"))
      (node (ref "R103") (pin "1") (pinfunction "1_1") (pintype "passive"))
    )
    (net (code "36") (name "/GPB3") (class "Default")
      (node (ref "IC2") (pin "4") (pinfunction "GPB3_4") (pintype "bidirectional"))
      (node (ref "Q12") (pin "2") (pinfunction "S_2") (pintype "passive"))
      (node (ref "R105") (pin "1") (pinfunction "1_1") (pintype "passive"))
    )
    (net (code "37") (name "/GPB4") (class "Default")
      (node (ref "IC2") (pin "5") (pinfunction "GPB4_5") (pintype "bidirectional"))
      (node (ref "Q13") (pin "2") (pinfunction "S_2") (pintype "passive"))
      (node (ref "R107") (pin "1") (pinfunction "1_1") (pintype "passive"))
    )
    (net (code "38") (name "/GPB5") (class "Default")
      (node (ref "IC2") (pin "6") (pinfunction "GPB5_6") (pintype "bidirectional"))
      (node (ref "Q14") (pin "2") (pinfunction "S_2") (pintype "passive"))
      (node (ref "R109") (pin "1") (pinfunction "1_1") (pintype "passive"))
    )
    (net (code "39") (name "/GPB6") (class "Default")
      (node (ref "IC2") (pin "7") (pinfunction "GPB6_7") (pintype "bidirectional"))
      (node (ref "Q15") (pin "2") (pinfunction "S_2") (pintype "passive"))
      (node (ref "R111") (pin "1") (pinfunction "1_1") (pintype "passive"))
    )
    (net (code "40") (name "/GPB7") (class "Default")
      (node (ref "IC2") (pin "8") (pinfunction "GPB7_8") (pintype "bidirectional"))
      (node (ref "Q16") (pin "2") (pinfunction "S_2") (pintype "passive"))
      (node (ref "R113") (pin "1") (pinfunction "1_1") (pintype "passive"))
    )
    (net (code "41") (name "/INTA") (class "Default")
      (node (ref "6_INTA") (pin "1") (pinfunction "3_1") (pintype "passive"))
      (node (ref "IC2") (pin "20") (pinfunction "INTA_20") (pintype "output"))
      (node (ref "IC6") (pin "6-OUT1D") (pinfunction "6-OUT1D_6-OUT1D") (pintype "bidirectional"))
    )
    (net (code "42") (name "/INTB") (class "Default")
      (node (ref "7_INTB") (pin "1") (pinfunction "3_1") (pintype "passive"))
      (node (ref "IC2") (pin "19") (pinfunction "INTB_19") (pintype "output"))
      (node (ref "IC6") (pin "7-RX2/OUT1A") (pinfunction "7-RX2/OUT1A_7-RX2/OUT1A") (pintype "bidirectional"))
    )
    (net (code "43") (name "/SPI_CS_DAC1") (class "Default")
      (node (ref "9_DAC_CS") (pin "1") (pinfunction "3_1") (pintype "passive"))
      (node (ref "IC11") (pin "9") (pinfunction "~{SYNC}_9") (pintype "input"))
      (node (ref "IC6") (pin "9-OUT1C") (pinfunction "9-OUT1C_9-OUT1C") (pintype "bidirectional"))
    )
    (net (code "44") (name "/SPI_CS_DAC2") (class "Default")
      (node (ref "8_DAC_CS") (pin "1") (pinfunction "3_1") (pintype "passive"))
      (node (ref "IC10") (pin "9") (pinfunction "~{SYNC}_9") (pintype "input"))
      (node (ref "IC6") (pin "8-TX2/IN1") (pinfunction "8-TX2/IN1_8-TX2/IN1") (pintype "bidirectional"))
    )
    (net (code "45") (name "/SPI_IO_CS") (class "Default")
      (node (ref "10_IO_CS") (pin "1") (pinfunction "3_1") (pintype "passive"))
      (node (ref "IC2") (pin "11") (pinfunction "~{CS}_11") (pintype "input"))
      (node (ref "IC6") (pin "10-CS\\MQSR") (pinfunction "10-CS/MQSR_10-CS\\MQSR") (pintype "bidirectional"))
    )
    (net (code "46") (name "/SPI_MISO") (class "Default")
      (node (ref "12_MISO") (pin "1") (pinfunction "3_1") (pintype "passive"))
      (node (ref "IC2") (pin "14") (pinfunction "SO_14") (pintype "output"))
      (node (ref "IC6") (pin "12-MISO/MQSL") (pinfunction "12-MISO/MQSL_12-MISO/MQSL") (pintype "bidirectional"))
    )
    (net (code "47") (name "/SPI_MOSI") (class "Default")
      (node (ref "11_MOSI") (pin "1") (pinfunction "3_1") (pintype "passive"))
      (node (ref "IC10") (pin "11") (pinfunction "DIN_11") (pintype "input"))
      (node (ref "IC11") (pin "11") (pinfunction "DIN_11") (pintype "input"))
      (node (ref "IC2") (pin "13") (pinfunction "SI_13") (pintype "input"))
      (node (ref "IC6") (pin "11-MOSI/CTX1") (pinfunction "11-MOSI/CTX1_11-MOSI/CTX1") (pintype "bidirectional"))
    )
    (net (code "48") (name "/SPI_SCK") (class "Default")
      (node (ref "13_SCK") (pin "1") (pinfunction "3_1") (pintype "passive"))
      (node (ref "IC10") (pin "10") (pinfunction "SCLK_10") (pintype "input"))
      (node (ref "IC11") (pin "10") (pinfunction "SCLK_10") (pintype "input"))
      (node (ref "IC2") (pin "12") (pinfunction "SCK_12") (pintype "input"))
      (node (ref "IC6") (pin "13-SCK/LED") (pinfunction "13-SCK/LED_13-SCK/LED") (pintype "bidirectional"))
    )
    (net (code "49") (name "5V") (class "Default")
      (node (ref "5V") (pin "1") (pinfunction "3_1") (pintype "passive"))
      (node (ref "5V1") (pin "1") (pinfunction "3_1") (pintype "passive"))
      (node (ref "5V2") (pin "1") (pinfunction "3_1") (pintype "passive"))
      (node (ref "5V3") (pin "1") (pinfunction "3_1") (pintype "passive"))
      (node (ref "C27") (pin "2") (pinfunction "2_2") (pintype "passive"))
      (node (ref "C3") (pin "+") (pinfunction "+_+") (pintype "passive"))
      (node (ref "IC6") (pin "VIN") (pinfunction "VIN_VIN") (pintype "bidirectional"))
      (node (ref "IC7") (pin "3") (pinfunction "VO_3") (pintype "passive"))
      (node (ref "R100") (pin "2") (pinfunction "2_2") (pintype "passive"))
      (node (ref "R102") (pin "2") (pinfunction "2_2") (pintype "passive"))
      (node (ref "R104") (pin "2") (pinfunction "2_2") (pintype "passive"))
      (node (ref "R106") (pin "2") (pinfunction "2_2") (pintype "passive"))
      (node (ref "R108") (pin "2") (pinfunction "2_2") (pintype "passive"))
      (node (ref "R110") (pin "2") (pinfunction "2_2") (pintype "passive"))
      (node (ref "R112") (pin "2") (pinfunction "2_2") (pintype "passive"))
      (node (ref "R114") (pin "2") (pinfunction "2_2") (pintype "passive"))
      (node (ref "R58") (pin "2") (pinfunction "2_2") (pintype "passive"))
      (node (ref "R60") (pin "2") (pinfunction "2_2") (pintype "passive"))
      (node (ref "R72") (pin "2") (pinfunction "2_2") (pintype "passive"))
      (node (ref "R74") (pin "2") (pinfunction "2_2") (pintype "passive"))
      (node (ref "R76") (pin "2") (pinfunction "2_2") (pintype "passive"))
      (node (ref "R78") (pin "2") (pinfunction "2_2") (pintype "passive"))
      (node (ref "R80") (pin "2") (pinfunction "2_2") (pintype "passive"))
      (node (ref "R99") (pin "2") (pinfunction "2_2") (pintype "passive"))
    )
    (net (code "50") (name "GND") (class "Default")
      (node (ref "C1") (pin "-") (pinfunction "-_-") (pintype "passive"))
      (node (ref "C15") (pin "1") (pinfunction "1_1") (pintype "passive"))
      (node (ref "C18") (pin "1") (pinfunction "1_1") (pintype "passive"))
      (node (ref "C2") (pin "+") (pinfunction "+_+") (pintype "passive"))
      (node (ref "C23") (pin "1") (pinfunction "1_1") (pintype "passive"))
      (node (ref "C24") (pin "2") (pinfunction "2_2") (pintype "passive"))
      (node (ref "C25") (pin "2") (pinfunction "2_2") (pintype "passive"))
      (node (ref "C26") (pin "1") (pinfunction "1_1") (pintype "passive"))
      (node (ref "C27") (pin "1") (pinfunction "1_1") (pintype "passive"))
      (node (ref "C3") (pin "-") (pinfunction "-_-") (pintype "passive"))
      (node (ref "C32") (pin "1") (pinfunction "1_1") (pintype "passive"))
      (node (ref "C33") (pin "2") (pinfunction "2_2") (pintype "passive"))
      (node (ref "C34") (pin "2") (pinfunction "2_2") (pintype "passive"))
      (node (ref "C6") (pin "1") (pinfunction "1_1") (pintype "passive"))
      (node (ref "GND") (pin "1") (pinfunction "3_1") (pintype "passive"))
      (node (ref "GND1") (pin "1") (pinfunction "3_1") (pintype "passive"))
      (node (ref "GND2") (pin "1") (pinfunction "3_1") (pintype "passive"))
      (node (ref "GND3") (pin "1") (pinfunction "3_1") (pintype "passive"))
      (node (ref "GND4") (pin "1") (pinfunction "3_1") (pintype "passive"))
      (node (ref "GND5") (pin "1") (pinfunction "3_1") (pintype "passive"))
      (node (ref "GND6") (pin "1") (pinfunction "3_1") (pintype "passive"))
      (node (ref "GND7") (pin "1") (pinfunction "3_1") (pintype "passive"))
      (node (ref "GND8") (pin "1") (pinfunction "3_1") (pintype "passive"))
      (node (ref "GND9") (pin "1") (pinfunction "3_1") (pintype "passive"))
      (node (ref "IC1") (pin "10") (pinfunction "+IN_10") (pintype "input"))
      (node (ref "IC1") (pin "12") (pinfunction "+IN_12") (pintype "input"))
      (node (ref "IC1") (pin "3") (pinfunction "+IN_3") (pintype "input"))
      (node (ref "IC1") (pin "5") (pinfunction "+IN_5") (pintype "input"))
      (node (ref "IC10") (pin "13") (pinfunction "A0_13") (pintype "input"))
      (node (ref "IC10") (pin "14") (pinfunction "A1_14") (pintype "input"))
      (node (ref "IC10") (pin "15") (pinfunction "~{ENABLE}_15") (pintype "input"))
      (node (ref "IC10") (pin "16") (pinfunction "LDAC_16") (pintype "input"))
      (node (ref "IC10") (pin "5") (pinfunction "VREFL_5") (pintype "input"))
      (node (ref "IC10") (pin "6") (pinfunction "GND_6") (pintype "power_in"))
      (node (ref "IC11") (pin "13") (pinfunction "A0_13") (pintype "input"))
      (node (ref "IC11") (pin "14") (pinfunction "A1_14") (pintype "input"))
      (node (ref "IC11") (pin "15") (pinfunction "~{ENABLE}_15") (pintype "input"))
      (node (ref "IC11") (pin "16") (pinfunction "LDAC_16") (pintype "input"))
      (node (ref "IC11") (pin "5") (pinfunction "VREFL_5") (pintype "input"))
      (node (ref "IC11") (pin "6") (pinfunction "GND_6") (pintype "power_in"))
      (node (ref "IC2") (pin "10") (pinfunction "VSS_10") (pintype "power_in"))
      (node (ref "IC2") (pin "15") (pinfunction "A0_15") (pintype "input"))
      (node (ref "IC2") (pin "16") (pinfunction "A1_16") (pintype "input"))
      (node (ref "IC2") (pin "17") (pinfunction "A2_17") (pintype "input"))
      (node (ref "IC3") (pin "10") (pinfunction "+IN_10") (pintype "input"))
      (node (ref "IC3") (pin "11") (pinfunction "V-_11") (pintype "power_in"))
      (node (ref "IC3") (pin "12") (pinfunction "+IN_12") (pintype "input"))
      (node (ref "IC3") (pin "3") (pinfunction "+IN_3") (pintype "input"))
      (node (ref "IC3") (pin "5") (pinfunction "+IN_5") (pintype "input"))
      (node (ref "IC4") (pin "10") (pinfunction "+IN_10") (pintype "input"))
      (node (ref "IC4") (pin "11") (pinfunction "V-_11") (pintype "power_in"))
      (node (ref "IC4") (pin "12") (pinfunction "+IN_12") (pintype "input"))
      (node (ref "IC4") (pin "3") (pinfunction "+IN_3") (pintype "input"))
      (node (ref "IC4") (pin "5") (pinfunction "+IN_5") (pintype "input"))
      (node (ref "IC5") (pin "10") (pinfunction "+IN_10") (pintype "input"))
      (node (ref "IC5") (pin "12") (pinfunction "+IN_12") (pintype "input"))
      (node (ref "IC5") (pin "3") (pinfunction "+IN_3") (pintype "input"))
      (node (ref "IC5") (pin "5") (pinfunction "+IN_5") (pintype "input"))
      (node (ref "IC6") (pin "GND1") (pinfunction "GND1_GND1") (pintype "bidirectional"))
      (node (ref "IC6") (pin "GND3") (pinfunction "GND3_GND3") (pintype "bidirectional"))
      (node (ref "IC6") (pin "GND6") (pinfunction "GND6_GND6") (pintype "bidirectional"))
      (node (ref "IC7") (pin "2") (pinfunction "GND_2") (pintype "passive"))
      (node (ref "IC8") (pin "1") (pinfunction "C_1") (pintype "input"))
      (node (ref "IC9") (pin "10") (pinfunction "+IN_10") (pintype "input"))
      (node (ref "IC9") (pin "11") (pinfunction "V-_11") (pintype "power_in"))
      (node (ref "IC9") (pin "12") (pinfunction "+IN_12") (pintype "input"))
      (node (ref "IC9") (pin "3") (pinfunction "+IN_3") (pintype "input"))
      (node (ref "IC9") (pin "5") (pinfunction "+IN_5") (pintype "input"))
    )
    (net (code "51") (name "Net-(0_RX-3)") (class "Default")
      (node (ref "0_RX") (pin "1") (pinfunction "3_1") (pintype "passive"))
      (node (ref "IC6") (pin "0-RX1/CS1/CRX2") (pinfunction "0-RX1/CS1/CRX2_0-RX1/CS1/CRX2") (pintype "bidirectional"))
    )
    (net (code "52") (name "Net-(1_TX-3)") (class "Default")
      (node (ref "1_TX") (pin "1") (pinfunction "3_1") (pintype "passive"))
      (node (ref "IC6") (pin "1-TX1/MISO1/CTX2") (pinfunction "1-TX1/MISO1/CTX2_1-TX1/MISO1/CTX2") (pintype "bidirectional"))
    )
    (net (code "53") (name "Net-(5-3)") (class "Default")
      (node (ref "5") (pin "1") (pinfunction "3_1") (pintype "passive"))
      (node (ref "IC6") (pin "5-IN2") (pinfunction "5-IN2_5-IN2") (pintype "bidirectional"))
    )
    (net (code "54") (name "Net-(18_SDA-3)") (class "Default")
      (node (ref "18_SDA") (pin "1") (pinfunction "3_1") (pintype "passive"))
      (node (ref "IC6") (pin "18-A4/SDA0") (pinfunction "18-A4/SDA0_18-A4/SDA0") (pintype "bidirectional"))
      (node (ref "R115") (pin "1") (pinfunction "1_1") (pintype "passive"))
    )
    (net (code "55") (name "Net-(19_SCL-3)") (class "Default")
      (node (ref "19_SCL") (pin "1") (pinfunction "3_1") (pintype "passive"))
      (node (ref "IC6") (pin "19-A5/SCL0") (pinfunction "19-A5/SCL0_19-A5/SCL0") (pintype "bidirectional"))
      (node (ref "R116") (pin "1") (pinfunction "1_1") (pintype "passive"))
    )
    (net (code "56") (name "Net-(28-3)") (class "Default")
      (node (ref "28") (pin "1") (pinfunction "3_1") (pintype "passive"))
      (node (ref "IC6") (pin "28-RX7") (pinfunction "28-RX7_28-RX7") (pintype "bidirectional"))
    )
    (net (code "57") (name "Net-(29-3)") (class "Default")
      (node (ref "29") (pin "1") (pinfunction "3_1") (pintype "passive"))
      (node (ref "IC6") (pin "29-TX7") (pinfunction "29-TX7_29-TX7") (pintype "bidirectional"))
    )
    (net (code "58") (name "Net-(30-3)") (class "Default")
      (node (ref "30") (pin "1") (pinfunction "3_1") (pintype "passive"))
      (node (ref "IC6") (pin "30-CRX3") (pinfunction "30-CRX3_30-CRX3") (pintype "bidirectional"))
    )
    (net (code "59") (name "Net-(31-3)") (class "Default")
      (node (ref "31") (pin "1") (pinfunction "3_1") (pintype "passive"))
      (node (ref "IC6") (pin "31-CTX3") (pinfunction "31-CTX3_31-CTX3") (pintype "bidirectional"))
    )
    (net (code "60") (name "Net-(32-3)") (class "Default")
      (node (ref "32") (pin "1") (pinfunction "3_1") (pintype "passive"))
      (node (ref "IC6") (pin "32-OUT1B") (pinfunction "32-OUT1B_32-OUT1B") (pintype "bidirectional"))
    )
    (net (code "61") (name "Net-(33-3)") (class "Default")
      (node (ref "33") (pin "1") (pinfunction "3_1") (pintype "passive"))
      (node (ref "IC6") (pin "33-MCLK2") (pinfunction "33-MCLK2_33-MCLK2") (pintype "bidirectional"))
    )
    (net (code "62") (name "Net-(34-3)") (class "Default")
      (node (ref "34") (pin "1") (pinfunction "3_1") (pintype "passive"))
      (node (ref "IC6") (pin "34-RX8") (pinfunction "34-RX8_34-RX8") (pintype "bidirectional"))
    )
    (net (code "63") (name "Net-(35-3)") (class "Default")
      (node (ref "35") (pin "1") (pinfunction "3_1") (pintype "passive"))
      (node (ref "IC6") (pin "35-TX8") (pinfunction "35/TX8_35-TX8") (pintype "bidirectional"))
    )
    (net (code "64") (name "Net-(36-3)") (class "Default")
      (node (ref "36") (pin "1") (pinfunction "3_1") (pintype "passive"))
      (node (ref "IC6") (pin "36-PWM") (pinfunction "36-PWM_36-PWM") (pintype "bidirectional"))
    )
    (net (code "65") (name "Net-(37-3)") (class "Default")
      (node (ref "37") (pin "1") (pinfunction "3_1") (pintype "passive"))
      (node (ref "IC6") (pin "37-PWM") (pinfunction "37-PWM_37-PWM") (pintype "bidirectional"))
    )
    (net (code "66") (name "Net-(38-3)") (class "Default")
      (node (ref "38") (pin "1") (pinfunction "3_1") (pintype "passive"))
      (node (ref "IC6") (pin "38-A14/CS/IN1") (pinfunction "38-A14/CS/IN1_38-A14/CS/IN1") (pintype "bidirectional"))
    )
    (net (code "67") (name "Net-(39-3)") (class "Default")
      (node (ref "39") (pin "1") (pinfunction "3_1") (pintype "passive"))
      (node (ref "IC6") (pin "39-A15/CS/OUT1A") (pinfunction "39-A15/CS/OUT1A_39-A15/CS/OUT1A") (pintype "bidirectional"))
    )
    (net (code "68") (name "Net-(40-3)") (class "Default")
      (node (ref "40") (pin "1") (pinfunction "3_1") (pintype "passive"))
      (node (ref "IC6") (pin "40-A16/CS1") (pinfunction "40-A16/CS1_40-A16/CS1") (pintype "bidirectional"))
    )
    (net (code "69") (name "Net-(41-3)") (class "Default")
      (node (ref "41") (pin "1") (pinfunction "3_1") (pintype "passive"))
      (node (ref "IC6") (pin "41-A17/MISO1") (pinfunction "41-A17/MISO1_41-A17/MISO1") (pintype "bidirectional"))
    )
    (net (code "70") (name "Net-(CV1-3)") (class "Default")
      (node (ref "CV1") (pin "1") (pinfunction "3_1") (pintype "passive"))
      (node (ref "R31") (pin "1") (pinfunction "1_1") (pintype "passive"))
    )
    (net (code "71") (name "Net-(CV1B-3)") (class "Default")
      (node (ref "CV1B") (pin "1") (pinfunction "3_1") (pintype "passive"))
      (node (ref "R23") (pin "1") (pinfunction "1_1") (pintype "passive"))
    )
    (net (code "72") (name "Net-(CV2-3)") (class "Default")
      (node (ref "CV2") (pin "1") (pinfunction "3_1") (pintype "passive"))
      (node (ref "R27") (pin "1") (pinfunction "1_1") (pintype "passive"))
    )
    (net (code "73") (name "Net-(CV2B-3)") (class "Default")
      (node (ref "CV2B") (pin "1") (pinfunction "3_1") (pintype "passive"))
      (node (ref "R28") (pin "1") (pinfunction "1_1") (pintype "passive"))
    )
    (net (code "74") (name "Net-(CV3-3)") (class "Default")
      (node (ref "CV3") (pin "1") (pinfunction "3_1") (pintype "passive"))
      (node (ref "R22") (pin "1") (pinfunction "1_1") (pintype "passive"))
    )
    (net (code "75") (name "Net-(CV3B-3)") (class "Default")
      (node (ref "CV3B") (pin "1") (pinfunction "3_1") (pintype "passive"))
      (node (ref "R32") (pin "1") (pinfunction "1_1") (pintype "passive"))
    )
    (net (code "76") (name "Net-(CV4-3)") (class "Default")
      (node (ref "CV4") (pin "1") (pinfunction "3_1") (pintype "passive"))
      (node (ref "R35") (pin "1") (pinfunction "1_1") (pintype "passive"))
    )
    (net (code "77") (name "Net-(CV4B-3)") (class "Default")
      (node (ref "CV4B") (pin "1") (pinfunction "3_1") (pintype "passive"))
      (node (ref "R36") (pin "1") (pinfunction "1_1") (pintype "passive"))
    )
    (net (code "78") (name "Net-(CV5-3)") (class "Default")
      (node (ref "CV5") (pin "1") (pinfunction "3_1") (pintype "passive"))
      (node (ref "R65") (pin "1") (pinfunction "1_1") (pintype "passive"))
    )
    (net (code "79") (name "Net-(CV6-3)") (class "Default")
      (node (ref "CV6") (pin "1") (pinfunction "3_1") (pintype "passive"))
      (node (ref "R62") (pin "1") (pinfunction "1_1") (pintype "passive"))
    )
    (net (code "80") (name "Net-(CV7-3)") (class "Default")
      (node (ref "CV7") (pin "1") (pinfunction "3_1") (pintype "passive"))
      (node (ref "R11") (pin "1") (pinfunction "1_1") (pintype "passive"))
    )
    (net (code "81") (name "Net-(CV8-3)") (class "Default")
      (node (ref "CV8") (pin "1") (pinfunction "3_1") (pintype "passive"))
      (node (ref "R69") (pin "1") (pinfunction "1_1") (pintype "passive"))
    )
    (net (code "82") (name "Net-(CV9-3)") (class "Default")
      (node (ref "CV9") (pin "1") (pinfunction "3_1") (pintype "passive"))
      (node (ref "R92") (pin "1") (pinfunction "1_1") (pintype "passive"))
    )
    (net (code "83") (name "Net-(CV9B-3)") (class "Default")
      (node (ref "CV9B") (pin "1") (pinfunction "3_1") (pintype "passive"))
      (node (ref "R12") (pin "1") (pinfunction "1_1") (pintype "passive"))
    )
    (net (code "84") (name "Net-(CV10-3)") (class "Default")
      (node (ref "CV10") (pin "1") (pinfunction "3_1") (pintype "passive"))
      (node (ref "R89") (pin "1") (pinfunction "1_1") (pintype "passive"))
    )
    (net (code "85") (name "Net-(CV10B-3)") (class "Default")
      (node (ref "CV10B") (pin "1") (pinfunction "3_1") (pintype "passive"))
      (node (ref "R63") (pin "1") (pinfunction "1_1") (pintype "passive"))
    )
    (net (code "86") (name "Net-(CV11-3)") (class "Default")
      (node (ref "CV11") (pin "1") (pinfunction "3_1") (pintype "passive"))
      (node (ref "R84") (pin "1") (pinfunction "1_1") (pintype "passive"))
    )
    (net (code "87") (name "Net-(CV11B-3)") (class "Default")
      (node (ref "CV11B") (pin "1") (pinfunction "3_1") (pintype "passive"))
      (node (ref "R66") (pin "1") (pinfunction "1_1") (pintype "passive"))
    )
    (net (code "88") (name "Net-(CV12-3)") (class "Default")
      (node (ref "CV12") (pin "1") (pinfunction "3_1") (pintype "passive"))
      (node (ref "R96") (pin "1") (pinfunction "1_1") (pintype "passive"))
    )
    (net (code "89") (name "Net-(CV12B-3)") (class "Default")
      (node (ref "CV12B") (pin "1") (pinfunction "3_1") (pintype "passive"))
      (node (ref "R70") (pin "1") (pinfunction "1_1") (pintype "passive"))
    )
    (net (code "90") (name "Net-(CV13B-3)") (class "Default")
      (node (ref "CV13B") (pin "1") (pinfunction "3_1") (pintype "passive"))
      (node (ref "R85") (pin "1") (pinfunction "1_1") (pintype "passive"))
    )
    (net (code "91") (name "Net-(CV14B-3)") (class "Default")
      (node (ref "CV14B") (pin "1") (pinfunction "3_1") (pintype "passive"))
      (node (ref "R90") (pin "1") (pinfunction "1_1") (pintype "passive"))
    )
    (net (code "92") (name "Net-(CV15B-3)") (class "Default")
      (node (ref "CV15B") (pin "1") (pinfunction "3_1") (pintype "passive"))
      (node (ref "R93") (pin "1") (pinfunction "1_1") (pintype "passive"))
    )
    (net (code "93") (name "Net-(CV16B-3)") (class "Default")
      (node (ref "CV16B") (pin "1") (pinfunction "3_1") (pintype "passive"))
      (node (ref "R97") (pin "1") (pinfunction "1_1") (pintype "passive"))
    )
    (net (code "94") (name "Net-(CVO1-3)") (class "Default")
      (node (ref "CVO1") (pin "1") (pinfunction "3_1") (pintype "passive"))
      (node (ref "R47") (pin "2") (pinfunction "2_2") (pintype "passive"))
    )
    (net (code "95") (name "Net-(CVO2-3)") (class "Default")
      (node (ref "CVO2") (pin "1") (pinfunction "3_1") (pintype "passive"))
      (node (ref "R38") (pin "2") (pinfunction "2_2") (pintype "passive"))
    )
    (net (code "96") (name "Net-(CVO3-3)") (class "Default")
      (node (ref "CVO3") (pin "1") (pinfunction "3_1") (pintype "passive"))
      (node (ref "R41") (pin "2") (pinfunction "2_2") (pintype "passive"))
    )
    (net (code "97") (name "Net-(CVO4-3)") (class "Default")
      (node (ref "CVO4") (pin "1") (pinfunction "3_1") (pintype "passive"))
      (node (ref "R44") (pin "2") (pinfunction "2_2") (pintype "passive"))
    )
    (net (code "98") (name "Net-(CVO5-3)") (class "Default")
      (node (ref "CVO5") (pin "1") (pinfunction "3_1") (pintype "passive"))
      (node (ref "R18") (pin "2") (pinfunction "2_2") (pintype "passive"))
    )
    (net (code "99") (name "Net-(CVO6-3)") (class "Default")
      (node (ref "CVO6") (pin "1") (pinfunction "3_1") (pintype "passive"))
      (node (ref "R3") (pin "2") (pinfunction "2_2") (pintype "passive"))
    )
    (net (code "100") (name "Net-(CVO7-3)") (class "Default")
      (node (ref "CVO7") (pin "1") (pinfunction "3_1") (pintype "passive"))
      (node (ref "R6") (pin "2") (pinfunction "2_2") (pintype "passive"))
    )
    (net (code "101") (name "Net-(CVO8-3)") (class "Default")
      (node (ref "CVO8") (pin "1") (pinfunction "3_1") (pintype "passive"))
      (node (ref "R14") (pin "2") (pinfunction "2_2") (pintype "passive"))
    )
    (net (code "102") (name "Net-(ENC1-3)") (class "Default")
      (node (ref "ENC1") (pin "1") (pinfunction "3_1") (pintype "passive"))
      (node (ref "IC6") (pin "3-LRCLK2") (pinfunction "3-LRCLK2_3-LRCLK2") (pintype "bidirectional"))
    )
    (net (code "103") (name "Net-(ENC2-3)") (class "Default")
      (node (ref "ENC2") (pin "1") (pinfunction "3_1") (pintype "passive"))
      (node (ref "IC6") (pin "4-BCLK2") (pinfunction "4-BCLK2_4-BCLK2") (pintype "bidirectional"))
    )
    (net (code "104") (name "Net-(ENCBTN-3)") (class "Default")
      (node (ref "ENCBTN") (pin "1") (pinfunction "3_1") (pintype "passive"))
      (node (ref "IC6") (pin "2-OUT2") (pinfunction "2-OUT2_2-OUT2") (pintype "bidirectional"))
    )
    (net (code "105") (name "Net-(IC1A--IN)") (class "Default")
      (node (ref "C4") (pin "1") (pinfunction "1_1") (pintype "passive"))
      (node (ref "IC1") (pin "2") (pinfunction "-IN_2") (pintype "input"))
      (node (ref "R1") (pin "1") (pinfunction "1_1") (pintype "passive"))
      (node (ref "R2") (pin "2") (pinfunction "2_2") (pintype "passive"))
      (node (ref "R48") (pin "2") (pinfunction "2_2") (pintype "passive"))
    )
    (net (code "106") (name "Net-(IC1A-OUT)") (class "Default")
      (node (ref "C4") (pin "2") (pinfunction "2_2") (pintype "passive"))
      (node (ref "IC1") (pin "1") (pinfunction "OUT_1") (pintype "output"))
      (node (ref "R1") (pin "2") (pinfunction "2_2") (pintype "passive"))
      (node (ref "R3") (pin "1") (pinfunction "1_1") (pintype "passive"))
    )
    (net (code "107") (name "Net-(IC1B--IN)") (class "Default")
      (node (ref "C5") (pin "1") (pinfunction "1_1") (pintype "passive"))
      (node (ref "IC1") (pin "6") (pinfunction "-IN_6") (pintype "input"))
      (node (ref "R4") (pin "1") (pinfunction "1_1") (pintype "passive"))
      (node (ref "R49") (pin "2") (pinfunction "2_2") (pintype "passive"))
      (node (ref "R5") (pin "2") (pinfunction "2_2") (pintype "passive"))
    )
    (net (code "108") (name "Net-(IC1B-OUT)") (class "Default")
      (node (ref "C5") (pin "2") (pinfunction "2_2") (pintype "passive"))
      (node (ref "IC1") (pin "7") (pinfunction "OUT_7") (pintype "output"))
      (node (ref "R4") (pin "2") (pinfunction "2_2") (pintype "passive"))
      (node (ref "R6") (pin "1") (pinfunction "1_1") (pintype "passive"))
    )
    (net (code "109") (name "Net-(IC1C--IN)") (class "Default")
      (node (ref "C8") (pin "1") (pinfunction "1_1") (pintype "passive"))
      (node (ref "IC1") (pin "9") (pinfunction "-IN_9") (pintype "input"))
      (node (ref "R10") (pin "2") (pinfunction "2_2") (pintype "passive"))
      (node (ref "R50") (pin "2") (pinfunction "2_2") (pintype "passive"))
      (node (ref "R9") (pin "1") (pinfunction "1_1") (pintype "passive"))
    )
    (net (code "110") (name "Net-(IC1C-OUT)") (class "Default")
      (node (ref "C8") (pin "2") (pinfunction "2_2") (pintype "passive"))
      (node (ref "IC1") (pin "8") (pinfunction "OUT_8") (pintype "output"))
      (node (ref "R14") (pin "1") (pinfunction "1_1") (pintype "passive"))
      (node (ref "R9") (pin "2") (pinfunction "2_2") (pintype "passive"))
    )
    (net (code "111") (name "Net-(IC1D--IN)") (class "Default")
      (node (ref "C9") (pin "1") (pinfunction "1_1") (pintype "passive"))
      (node (ref "IC1") (pin "13") (pinfunction "-IN_13") (pintype "input"))
      (node (ref "R16") (pin "1") (pinfunction "1_1") (pintype "passive"))
      (node (ref "R17") (pin "2") (pinfunction "2_2") (pintype "passive"))
      (node (ref "R51") (pin "2") (pinfunction "2_2") (pintype "passive"))
    )
    (net (code "112") (name "Net-(IC1D-OUT)") (class "Default")
      (node (ref "C9") (pin "2") (pinfunction "2_2") (pintype "passive"))
      (node (ref "IC1") (pin "14") (pinfunction "OUT_14") (pintype "output"))
      (node (ref "R16") (pin "2") (pinfunction "2_2") (pintype "passive"))
      (node (ref "R18") (pin "1") (pinfunction "1_1") (pintype "passive"))
    )
    (net (code "113") (name "Net-(IC2-~{RESET})") (class "Default")
      (node (ref "IC2") (pin "18") (pinfunction "~{RESET}_18") (pintype "input"))
      (node (ref "R82") (pin "2") (pinfunction "2_2") (pintype "passive"))
    )
    (net (code "114") (name "Net-(IC3A--IN)") (class "Default")
      (node (ref "C7") (pin "1") (pinfunction "1_1") (pintype "passive"))
      (node (ref "IC3") (pin "2") (pinfunction "-IN_2") (pintype "input"))
      (node (ref "R11") (pin "2") (pinfunction "2_2") (pintype "passive"))
      (node (ref "R12") (pin "2") (pinfunction "2_2") (pintype "passive"))
      (node (ref "R13") (pin "2") (pinfunction "2_2") (pintype "passive"))
      (node (ref "R8") (pin "1") (pinfunction "1_1") (pintype "passive"))
    )
    (net (code "115") (name "Net-(IC3B--IN)") (class "Default")
      (node (ref "C10") (pin "1") (pinfunction "1_1") (pintype "passive"))
      (node (ref "IC3") (pin "6") (pinfunction "-IN_6") (pintype "input"))
      (node (ref "R15") (pin "1") (pinfunction "1_1") (pintype "passive"))
      (node (ref "R29") (pin "2") (pinfunction "2_2") (pintype "passive"))
      (node (ref "R62") (pin "2") (pinfunction "2_2") (pintype "passive"))
      (node (ref "R63") (pin "2") (pinfunction "2_2") (pintype "passive"))
    )
    (net (code "116") (name "Net-(IC3C--IN)") (class "Default")
      (node (ref "C11") (pin "1") (pinfunction "1_1") (pintype "passive"))
      (node (ref "IC3") (pin "9") (pinfunction "-IN_9") (pintype "input"))
      (node (ref "R64") (pin "1") (pinfunction "1_1") (pintype "passive"))
      (node (ref "R65") (pin "2") (pinfunction "2_2") (pintype "passive"))
      (node (ref "R66") (pin "2") (pinfunction "2_2") (pintype "passive"))
      (node (ref "R67") (pin "2") (pinfunction "2_2") (pintype "passive"))
    )
    (net (code "117") (name "Net-(IC3D--IN)") (class "Default")
      (node (ref "C14") (pin "1") (pinfunction "1_1") (pintype "passive"))
      (node (ref "IC3") (pin "13") (pinfunction "-IN_13") (pintype "input"))
      (node (ref "R68") (pin "1") (pinfunction "1_1") (pintype "passive"))
      (node (ref "R69") (pin "2") (pinfunction "2_2") (pintype "passive"))
      (node (ref "R70") (pin "2") (pinfunction "2_2") (pintype "passive"))
      (node (ref "R71") (pin "2") (pinfunction "2_2") (pintype "passive"))
    )
    (net (code "118") (name "Net-(IC4A--IN)") (class "Default")
      (node (ref "C16") (pin "1") (pinfunction "1_1") (pintype "passive"))
      (node (ref "IC4") (pin "2") (pinfunction "-IN_2") (pintype "input"))
      (node (ref "R21") (pin "1") (pinfunction "1_1") (pintype "passive"))
      (node (ref "R22") (pin "2") (pinfunction "2_2") (pintype "passive"))
      (node (ref "R23") (pin "2") (pinfunction "2_2") (pintype "passive"))
      (node (ref "R24") (pin "2") (pinfunction "2_2") (pintype "passive"))
    )
    (net (code "119") (name "Net-(IC4B--IN)") (class "Default")
      (node (ref "C17") (pin "1") (pinfunction "1_1") (pintype "passive"))
      (node (ref "IC4") (pin "6") (pinfunction "-IN_6") (pintype "input"))
      (node (ref "R25") (pin "1") (pinfunction "1_1") (pintype "passive"))
      (node (ref "R26") (pin "2") (pinfunction "2_2") (pintype "passive"))
      (node (ref "R27") (pin "2") (pinfunction "2_2") (pintype "passive"))
      (node (ref "R28") (pin "2") (pinfunction "2_2") (pintype "passive"))
    )
    (net (code "120") (name "Net-(IC4C--IN)") (class "Default")
      (node (ref "C20") (pin "1") (pinfunction "1_1") (pintype "passive"))
      (node (ref "IC4") (pin "9") (pinfunction "-IN_9") (pintype "input"))
      (node (ref "R30") (pin "1") (pinfunction "1_1") (pintype "passive"))
      (node (ref "R31") (pin "2") (pinfunction "2_2") (pintype "passive"))
      (node (ref "R32") (pin "2") (pinfunction "2_2") (pintype "passive"))
      (node (ref "R33") (pin "2") (pinfunction "2_2") (pintype "passive"))
    )
    (net (code "121") (name "Net-(IC4D--IN)") (class "Default")
      (node (ref "C21") (pin "1") (pinfunction "1_1") (pintype "passive"))
      (node (ref "IC4") (pin "13") (pinfunction "-IN_13") (pintype "input"))
      (node (ref "R34") (pin "1") (pinfunction "1_1") (pintype "passive"))
      (node (ref "R35") (pin "2") (pinfunction "2_2") (pintype "passive"))
      (node (ref "R36") (pin "2") (pinfunction "2_2") (pintype "passive"))
      (node (ref "R37") (pin "2") (pinfunction "2_2") (pintype "passive"))
    )
    (net (code "122") (name "Net-(IC5A--IN)") (class "Default")
      (node (ref "C12") (pin "1") (pinfunction "1_1") (pintype "passive"))
      (node (ref "IC5") (pin "2") (pinfunction "-IN_2") (pintype "input"))
      (node (ref "R19") (pin "1") (pinfunction "1_1") (pintype "passive"))
      (node (ref "R20") (pin "2") (pinfunction "2_2") (pintype "passive"))
      (node (ref "R52") (pin "2") (pinfunction "2_2") (pintype "passive"))
    )
    (net (code "123") (name "Net-(IC5A-OUT)") (class "Default")
      (node (ref "C12") (pin "2") (pinfunction "2_2") (pintype "passive"))
      (node (ref "IC5") (pin "1") (pinfunction "OUT_1") (pintype "output"))
      (node (ref "R19") (pin "2") (pinfunction "2_2") (pintype "passive"))
      (node (ref "R38") (pin "1") (pinfunction "1_1") (pintype "passive"))
    )
    (net (code "124") (name "Net-(IC5B--IN)") (class "Default")
      (node (ref "C13") (pin "1") (pinfunction "1_1") (pintype "passive"))
      (node (ref "IC5") (pin "6") (pinfunction "-IN_6") (pintype "input"))
      (node (ref "R39") (pin "1") (pinfunction "1_1") (pintype "passive"))
      (node (ref "R40") (pin "2") (pinfunction "2_2") (pintype "passive"))
      (node (ref "R53") (pin "2") (pinfunction "2_2") (pintype "passive"))
    )
    (net (code "125") (name "Net-(IC5B-OUT)") (class "Default")
      (node (ref "C13") (pin "2") (pinfunction "2_2") (pintype "passive"))
      (node (ref "IC5") (pin "7") (pinfunction "OUT_7") (pintype "output"))
      (node (ref "R39") (pin "2") (pinfunction "2_2") (pintype "passive"))
      (node (ref "R41") (pin "1") (pinfunction "1_1") (pintype "passive"))
    )
    (net (code "126") (name "Net-(IC5C--IN)") (class "Default")
      (node (ref "C19") (pin "1") (pinfunction "1_1") (pintype "passive"))
      (node (ref "IC5") (pin "9") (pinfunction "-IN_9") (pintype "input"))
      (node (ref "R42") (pin "1") (pinfunction "1_1") (pintype "passive"))
      (node (ref "R43") (pin "2") (pinfunction "2_2") (pintype "passive"))
      (node (ref "R54") (pin "2") (pinfunction "2_2") (pintype "passive"))
    )
    (net (code "127") (name "Net-(IC5C-OUT)") (class "Default")
      (node (ref "C19") (pin "2") (pinfunction "2_2") (pintype "passive"))
      (node (ref "IC5") (pin "8") (pinfunction "OUT_8") (pintype "output"))
      (node (ref "R42") (pin "2") (pinfunction "2_2") (pintype "passive"))
      (node (ref "R44") (pin "1") (pinfunction "1_1") (pintype "passive"))
    )
    (net (code "128") (name "Net-(IC5D--IN)") (class "Default")
      (node (ref "C22") (pin "1") (pinfunction "1_1") (pintype "passive"))
      (node (ref "IC5") (pin "13") (pinfunction "-IN_13") (pintype "input"))
      (node (ref "R45") (pin "1") (pinfunction "1_1") (pintype "passive"))
      (node (ref "R46") (pin "2") (pinfunction "2_2") (pintype "passive"))
      (node (ref "R55") (pin "2") (pinfunction "2_2") (pintype "passive"))
    )
    (net (code "129") (name "Net-(IC5D-OUT)") (class "Default")
      (node (ref "C22") (pin "2") (pinfunction "2_2") (pintype "passive"))
      (node (ref "IC5") (pin "14") (pinfunction "OUT_14") (pintype "output"))
      (node (ref "R45") (pin "2") (pinfunction "2_2") (pintype "passive"))
      (node (ref "R47") (pin "1") (pinfunction "1_1") (pintype "passive"))
    )
    (net (code "130") (name "Net-(IC7-VI)") (class "Default")
      (node (ref "IC7") (pin "1") (pinfunction "VI_1") (pintype "input"))
      (node (ref "L1") (pin "2") (pinfunction "2_2") (pintype "passive"))
    )
    (net (code "131") (name "Net-(IC9A--IN)") (class "Default")
      (node (ref "C28") (pin "1") (pinfunction "1_1") (pintype "passive"))
      (node (ref "IC9") (pin "2") (pinfunction "-IN_2") (pintype "input"))
      (node (ref "R83") (pin "1") (pinfunction "1_1") (pintype "passive"))
      (node (ref "R84") (pin "2") (pinfunction "2_2") (pintype "passive"))
      (node (ref "R85") (pin "2") (pinfunction "2_2") (pintype "passive"))
      (node (ref "R86") (pin "2") (pinfunction "2_2") (pintype "passive"))
    )
    (net (code "132") (name "Net-(IC9B--IN)") (class "Default")
      (node (ref "C29") (pin "1") (pinfunction "1_1") (pintype "passive"))
      (node (ref "IC9") (pin "6") (pinfunction "-IN_6") (pintype "input"))
      (node (ref "R87") (pin "1") (pinfunction "1_1") (pintype "passive"))
      (node (ref "R88") (pin "2") (pinfunction "2_2") (pintype "passive"))
      (node (ref "R89") (pin "2") (pinfunction "2_2") (pintype "passive"))
      (node (ref "R90") (pin "2") (pinfunction "2_2") (pintype "passive"))
    )
    (net (code "133") (name "Net-(IC9C--IN)") (class "Default")
      (node (ref "C30") (pin "1") (pinfunction "1_1") (pintype "passive"))
      (node (ref "IC9") (pin "9") (pinfunction "-IN_9") (pintype "input"))
      (node (ref "R91") (pin "1") (pinfunction "1_1") (pintype "passive"))
      (node (ref "R92") (pin "2") (pinfunction "2_2") (pintype "passive"))
      (node (ref "R93") (pin "2") (pinfunction "2_2") (pintype "passive"))
      (node (ref "R94") (pin "2") (pinfunction "2_2") (pintype "passive"))
    )
    (net (code "134") (name "Net-(IC9D--IN)") (class "Default")
      (node (ref "C31") (pin "1") (pinfunction "1_1") (pintype "passive"))
      (node (ref "IC9") (pin "13") (pinfunction "-IN_13") (pintype "input"))
      (node (ref "R95") (pin "1") (pinfunction "1_1") (pintype "passive"))
      (node (ref "R96") (pin "2") (pinfunction "2_2") (pintype "passive"))
      (node (ref "R97") (pin "2") (pinfunction "2_2") (pintype "passive"))
      (node (ref "R98") (pin "2") (pinfunction "2_2") (pintype "passive"))
    )
    (net (code "135") (name "Net-(IC10-VREFH{slash}VREFOUT)") (class "Default")
      (node (ref "C34") (pin "1") (pinfunction "1_1") (pintype "passive"))
      (node (ref "IC10") (pin "3") (pinfunction "VREFH/VREFOUT_3") (pintype "bidirectional"))
    )
    (net (code "136") (name "Net-(IC11-VREFH{slash}VREFOUT)") (class "Default")
      (node (ref "C33") (pin "1") (pinfunction "1_1") (pintype "passive"))
      (node (ref "IC11") (pin "3") (pinfunction "VREFH/VREFOUT_3") (pintype "bidirectional"))
    )
    (net (code "137") (name "Net-(IO1-3)") (class "Default")
      (node (ref "IO1") (pin "1") (pinfunction "3_1") (pintype "passive"))
      (node (ref "Q9") (pin "3") (pinfunction "D_3") (pintype "passive"))
      (node (ref "R100") (pin "1") (pinfunction "1_1") (pintype "passive"))
    )
    (net (code "138") (name "Net-(IO2-3)") (class "Default")
      (node (ref "IO2") (pin "1") (pinfunction "3_1") (pintype "passive"))
      (node (ref "Q10") (pin "3") (pinfunction "D_3") (pintype "passive"))
      (node (ref "R102") (pin "1") (pinfunction "1_1") (pintype "passive"))
    )
    (net (code "139") (name "Net-(IO3-3)") (class "Default")
      (node (ref "IO3") (pin "1") (pinfunction "3_1") (pintype "passive"))
      (node (ref "Q11") (pin "3") (pinfunction "D_3") (pintype "passive"))
      (node (ref "R104") (pin "1") (pinfunction "1_1") (pintype "passive"))
    )
    (net (code "140") (name "Net-(IO4-3)") (class "Default")
      (node (ref "IO4") (pin "1") (pinfunction "3_1") (pintype "passive"))
      (node (ref "Q12") (pin "3") (pinfunction "D_3") (pintype "passive"))
      (node (ref "R106") (pin "1") (pinfunction "1_1") (pintype "passive"))
    )
    (net (code "141") (name "Net-(IO5-3)") (class "Default")
      (node (ref "IO5") (pin "1") (pinfunction "3_1") (pintype "passive"))
      (node (ref "Q13") (pin "3") (pinfunction "D_3") (pintype "passive"))
      (node (ref "R108") (pin "1") (pinfunction "1_1") (pintype "passive"))
    )
    (net (code "142") (name "Net-(IO6-3)") (class "Default")
      (node (ref "IO6") (pin "1") (pinfunction "3_1") (pintype "passive"))
      (node (ref "Q14") (pin "3") (pinfunction "D_3") (pintype "passive"))
      (node (ref "R110") (pin "1") (pinfunction "1_1") (pintype "passive"))
    )
    (net (code "143") (name "Net-(IO7-3)") (class "Default")
      (node (ref "IO7") (pin "1") (pinfunction "3_1") (pintype "passive"))
      (node (ref "Q15") (pin "3") (pinfunction "D_3") (pintype "passive"))
      (node (ref "R112") (pin "1") (pinfunction "1_1") (pintype "passive"))
    )
    (net (code "144") (name "Net-(IO8-3)") (class "Default")
      (node (ref "IO8") (pin "1") (pinfunction "3_1") (pintype "passive"))
      (node (ref "Q16") (pin "3") (pinfunction "D_3") (pintype "passive"))
      (node (ref "R114") (pin "1") (pinfunction "1_1") (pintype "passive"))
    )
    (net (code "145") (name "Net-(IO9-3)") (class "Default")
      (node (ref "IO9") (pin "1") (pinfunction "3_1") (pintype "passive"))
      (node (ref "Q1") (pin "3") (pinfunction "D_3") (pintype "passive"))
      (node (ref "R99") (pin "1") (pinfunction "1_1") (pintype "passive"))
    )
    (net (code "146") (name "Net-(IO10-3)") (class "Default")
      (node (ref "IO10") (pin "1") (pinfunction "3_1") (pintype "passive"))
      (node (ref "Q2") (pin "3") (pinfunction "D_3") (pintype "passive"))
      (node (ref "R58") (pin "1") (pinfunction "1_1") (pintype "passive"))
    )
    (net (code "147") (name "Net-(IO11-3)") (class "Default")
      (node (ref "IO11") (pin "1") (pinfunction "3_1") (pintype "passive"))
      (node (ref "Q3") (pin "3") (pinfunction "D_3") (pintype "passive"))
      (node (ref "R60") (pin "1") (pinfunction "1_1") (pintype "passive"))
    )
    (net (code "148") (name "Net-(IO12-3)") (class "Default")
      (node (ref "IO12") (pin "1") (pinfunction "3_1") (pintype "passive"))
      (node (ref "Q4") (pin "3") (pinfunction "D_3") (pintype "passive"))
      (node (ref "R72") (pin "1") (pinfunction "1_1") (pintype "passive"))
    )
    (net (code "149") (name "Net-(IO13-3)") (class "Default")
      (node (ref "IO13") (pin "1") (pinfunction "3_1") (pintype "passive"))
      (node (ref "Q5") (pin "3") (pinfunction "D_3") (pintype "passive"))
      (node (ref "R74") (pin "1") (pinfunction "1_1") (pintype "passive"))
    )
    (net (code "150") (name "Net-(IO14-3)") (class "Default")
      (node (ref "IO14") (pin "1") (pinfunction "3_1") (pintype "passive"))
      (node (ref "Q6") (pin "3") (pinfunction "D_3") (pintype "passive"))
      (node (ref "R76") (pin "1") (pinfunction "1_1") (pintype "passive"))
    )
    (net (code "151") (name "Net-(IO15-3)") (class "Default")
      (node (ref "IO15") (pin "1") (pinfunction "3_1") (pintype "passive"))
      (node (ref "Q7") (pin "3") (pinfunction "D_3") (pintype "passive"))
      (node (ref "R78") (pin "1") (pinfunction "1_1") (pintype "passive"))
    )
    (net (code "152") (name "Net-(IO16-3)") (class "Default")
      (node (ref "IO16") (pin "1") (pinfunction "3_1") (pintype "passive"))
      (node (ref "Q8") (pin "3") (pinfunction "D_3") (pintype "passive"))
      (node (ref "R80") (pin "1") (pinfunction "1_1") (pintype "passive"))
    )
    (net (code "153") (name "unconnected-(IC6-Pad3V3-1)") (class "Default")
      (node (ref "IC6") (pin "3V3-1") (pinfunction "3V3-1_3V3-1") (pintype "bidirectional"))
    )
    (net (code "154") (name "unconnected-(P1-3-Pad1)") (class "Default")
      (node (ref "P1") (pin "1") (pinfunction "3_1") (pintype "passive"))
    )
    (net (code "155") (name "unconnected-(P2-3-Pad1)") (class "Default")
      (node (ref "P2") (pin "1") (pinfunction "3_1") (pintype "passive"))
    )
    (net (code "156") (name "unconnected-(P3-3-Pad1)") (class "Default")
      (node (ref "P3") (pin "1") (pinfunction "3_1") (pintype "passive"))
    )
    (net (code "157") (name "unconnected-(P4-3-Pad1)") (class "Default")
      (node (ref "P4") (pin "1") (pinfunction "3_1") (pintype "passive"))
    )
    (net (code "158") (name "unconnected-(P5-3-Pad1)") (class "Default")
      (node (ref "P5") (pin "1") (pinfunction "3_1") (pintype "passive"))
    )
    (net (code "159") (name "unconnected-(P6-3-Pad1)") (class "Default")
      (node (ref "P6") (pin "1") (pinfunction "3_1") (pintype "passive"))
    )
    (net (code "160") (name "unconnected-(P7-3-Pad1)") (class "Default")
      (node (ref "P7") (pin "1") (pinfunction "3_1") (pintype "passive"))
    )
    (net (code "161") (name "unconnected-(P8-3-Pad1)") (class "Default")
      (node (ref "P8") (pin "1") (pinfunction "3_1") (pintype "passive"))
    )
    (net (code "162") (name "unconnected-(P9-3-Pad1)") (class "Default")
      (node (ref "P9") (pin "1") (pinfunction "3_1") (pintype "passive"))
    )
    (net (code "163") (name "unconnected-(P10-3-Pad1)") (class "Default")
      (node (ref "P10") (pin "1") (pinfunction "3_1") (pintype "passive"))
    )
    (net (code "164") (name "unconnected-(P11-3-Pad1)") (class "Default")
      (node (ref "P11") (pin "1") (pinfunction "3_1") (pintype "passive"))
    )
    (net (code "165") (name "unconnected-(P12-3-Pad1)") (class "Default")
      (node (ref "P12") (pin "1") (pinfunction "3_1") (pintype "passive"))
    )
    (net (code "166") (name "unconnected-(P13-3-Pad1)") (class "Default")
      (node (ref "P13") (pin "1") (pinfunction "3_1") (pintype "passive"))
    )
    (net (code "167") (name "unconnected-(P14-3-Pad1)") (class "Default")
      (node (ref "P14") (pin "1") (pinfunction "3_1") (pintype "passive"))
    )
    (net (code "168") (name "unconnected-(P15-3-Pad1)") (class "Default")
      (node (ref "P15") (pin "1") (pinfunction "3_1") (pintype "passive"))
    )
    (net (code "169") (name "unconnected-(P16-3-Pad1)") (class "Default")
      (node (ref "P16") (pin "1") (pinfunction "3_1") (pintype "passive"))
    )
    (net (code "170") (name "unconnected-(P17-3-Pad1)") (class "Default")
      (node (ref "P17") (pin "1") (pinfunction "3_1") (pintype "passive"))
    )
    (net (code "171") (name "unconnected-(P18-3-Pad1)") (class "Default")
      (node (ref "P18") (pin "1") (pinfunction "3_1") (pintype "passive"))
    )
    (net (code "172") (name "unconnected-(P19-3-Pad1)") (class "Default")
      (node (ref "P19") (pin "1") (pinfunction "3_1") (pintype "passive"))
    )
    (net (code "173") (name "unconnected-(P20-3-Pad1)") (class "Default")
      (node (ref "P20") (pin "1") (pinfunction "3_1") (pintype "passive"))
    )
    (net (code "174") (name "unconnected-(P21-3-Pad1)") (class "Default")
      (node (ref "P21") (pin "1") (pinfunction "3_1") (pintype "passive"))
    )
    (net (code "175") (name "unconnected-(P22-3-Pad1)") (class "Default")
      (node (ref "P22") (pin "1") (pinfunction "3_1") (pintype "passive"))
    )
    (net (code "176") (name "unconnected-(P23-3-Pad1)") (class "Default")
      (node (ref "P23") (pin "1") (pinfunction "3_1") (pintype "passive"))
    )
    (net (code "177") (name "unconnected-(P24-3-Pad1)") (class "Default")
      (node (ref "P24") (pin "1") (pinfunction "3_1") (pintype "passive"))
    )
    (net (code "178") (name "unconnected-(P25-3-Pad1)") (class "Default")
      (node (ref "P25") (pin "1") (pinfunction "3_1") (pintype "passive"))
    )
    (net (code "179") (name "unconnected-(P26-3-Pad1)") (class "Default")
      (node (ref "P26") (pin "1") (pinfunction "3_1") (pintype "passive"))
    )
    (net (code "180") (name "unconnected-(P27-3-Pad1)") (class "Default")
      (node (ref "P27") (pin "1") (pinfunction "3_1") (pintype "passive"))
    )
    (net (code "181") (name "unconnected-(P28-3-Pad1)") (class "Default")
      (node (ref "P28") (pin "1") (pinfunction "3_1") (pintype "passive"))
    )
    (net (code "182") (name "unconnected-(P29-3-Pad1)") (class "Default")
      (node (ref "P29") (pin "1") (pinfunction "3_1") (pintype "passive"))
    )
    (net (code "183") (name "unconnected-(P30-3-Pad1)") (class "Default")
      (node (ref "P30") (pin "1") (pinfunction "3_1") (pintype "passive"))
    )
    (net (code "184") (name "unconnected-(P31-3-Pad1)") (class "Default")
      (node (ref "P31") (pin "1") (pinfunction "3_1") (pintype "passive"))
    )
    (net (code "185") (name "unconnected-(P32-3-Pad1)") (class "Default")
      (node (ref "P32") (pin "1") (pinfunction "3_1") (pintype "passive"))
    )
    (net (code "186") (name "unconnected-(P33-3-Pad1)") (class "Default")
      (node (ref "P33") (pin "1") (pinfunction "3_1") (pintype "passive"))
    )
    (net (code "187") (name "unconnected-(P34-3-Pad1)") (class "Default")
      (node (ref "P34") (pin "1") (pinfunction "3_1") (pintype "passive"))
    )
    (net (code "188") (name "unconnected-(P35-3-Pad1)") (class "Default")
      (node (ref "P35") (pin "1") (pinfunction "3_1") (pintype "passive"))
    )
    (net (code "189") (name "unconnected-(P36-3-Pad1)") (class "Default")
      (node (ref "P36") (pin "1") (pinfunction "3_1") (pintype "passive"))
    )
    (net (code "190") (name "unconnected-(P37-3-Pad1)") (class "Default")
      (node (ref "P37") (pin "1") (pinfunction "3_1") (pintype "passive"))
    )
    (net (code "191") (name "unconnected-(P38-3-Pad1)") (class "Default")
      (node (ref "P38") (pin "1") (pinfunction "3_1") (pintype "passive"))
    )
    (net (code "192") (name "unconnected-(P39-3-Pad1)") (class "Default")
      (node (ref "P39") (pin "1") (pinfunction "3_1") (pintype "passive"))
    )
    (net (code "193") (name "unconnected-(P40-3-Pad1)") (class "Default")
      (node (ref "P40") (pin "1") (pinfunction "3_1") (pintype "passive"))
    )
    (net (code "194") (name "unconnected-(P41-3-Pad1)") (class "Default")
      (node (ref "P41") (pin "1") (pinfunction "3_1") (pintype "passive"))
    )
    (net (code "195") (name "unconnected-(P42-3-Pad1)") (class "Default")
      (node (ref "P42") (pin "1") (pinfunction "3_1") (pintype "passive"))
    )
    (net (code "196") (name "unconnected-(P43-3-Pad1)") (class "Default")
      (node (ref "P43") (pin "1") (pinfunction "3_1") (pintype "passive"))
    )
    (net (code "197") (name "unconnected-(P44-3-Pad1)") (class "Default")
      (node (ref "P44") (pin "1") (pinfunction "3_1") (pintype "passive"))
    )
    (net (code "198") (name "unconnected-(P45-3-Pad1)") (class "Default")
      (node (ref "P45") (pin "1") (pinfunction "3_1") (pintype "passive"))
    )
    (net (code "199") (name "unconnected-(P46-3-Pad1)") (class "Default")
      (node (ref "P46") (pin "1") (pinfunction "3_1") (pintype "passive"))
    )
    (net (code "200") (name "unconnected-(P47-3-Pad1)") (class "Default")
      (node (ref "P47") (pin "1") (pinfunction "3_1") (pintype "passive"))
    )
    (net (code "201") (name "unconnected-(P48-3-Pad1)") (class "Default")
      (node (ref "P48") (pin "1") (pinfunction "3_1") (pintype "passive"))
    )
    (net (code "202") (name "unconnected-(P49-3-Pad1)") (class "Default")
      (node (ref "P49") (pin "1") (pinfunction "3_1") (pintype "passive"))
    )
    (net (code "203") (name "unconnected-(P50-3-Pad1)") (class "Default")
      (node (ref "P50") (pin "1") (pinfunction "3_1") (pintype "passive"))
    )
  )
)
